# ES_Daisy_Petal_Rev5.net
KiCad netlist of a schematic drawn in EAGLE
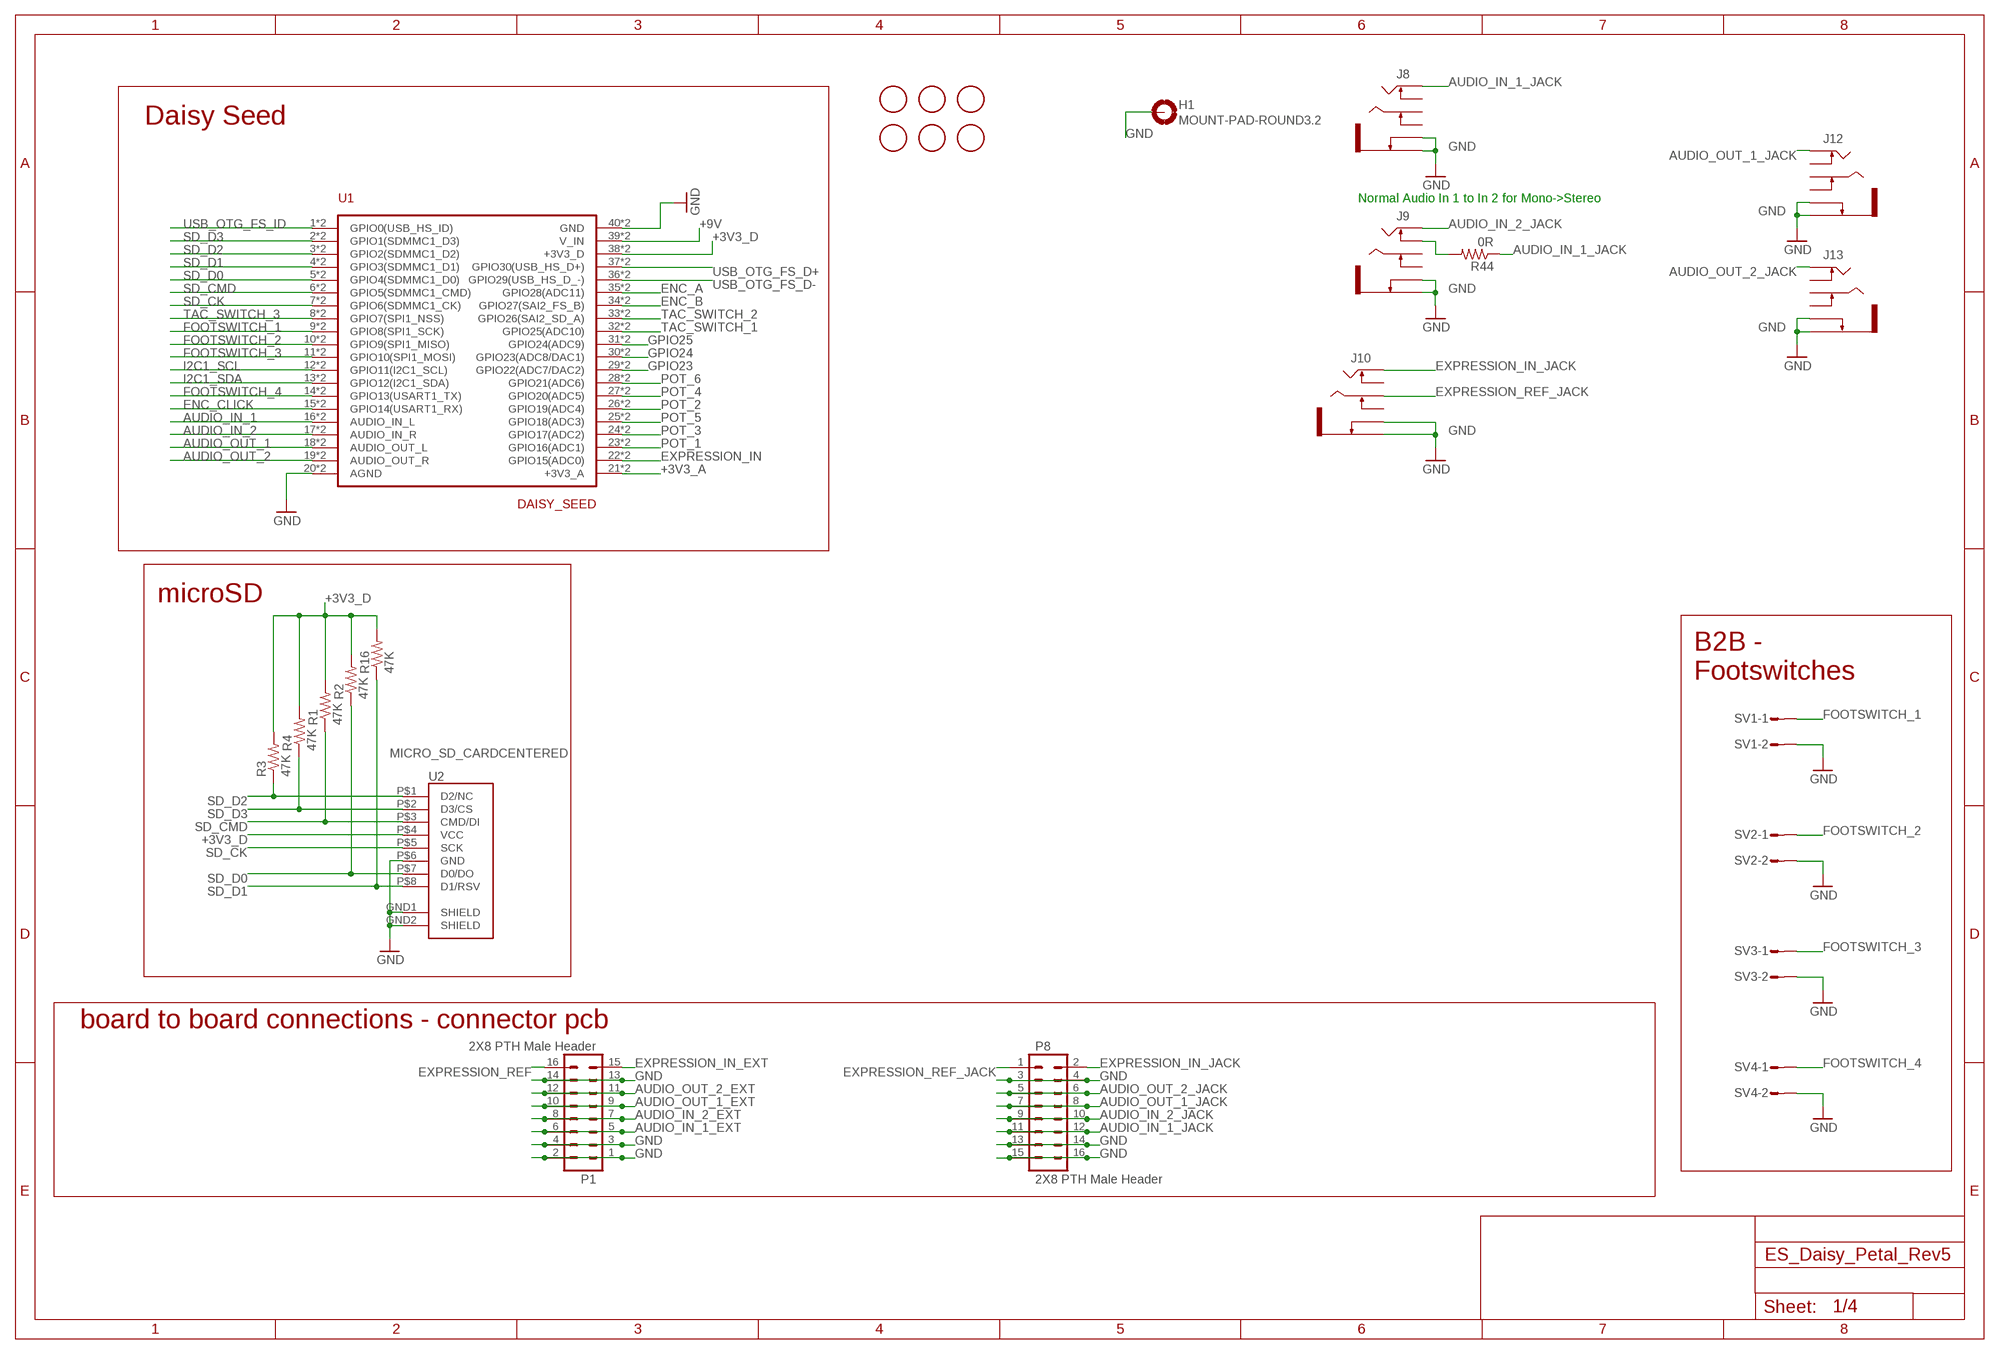
[diagram p0: schematic, sheet 1]
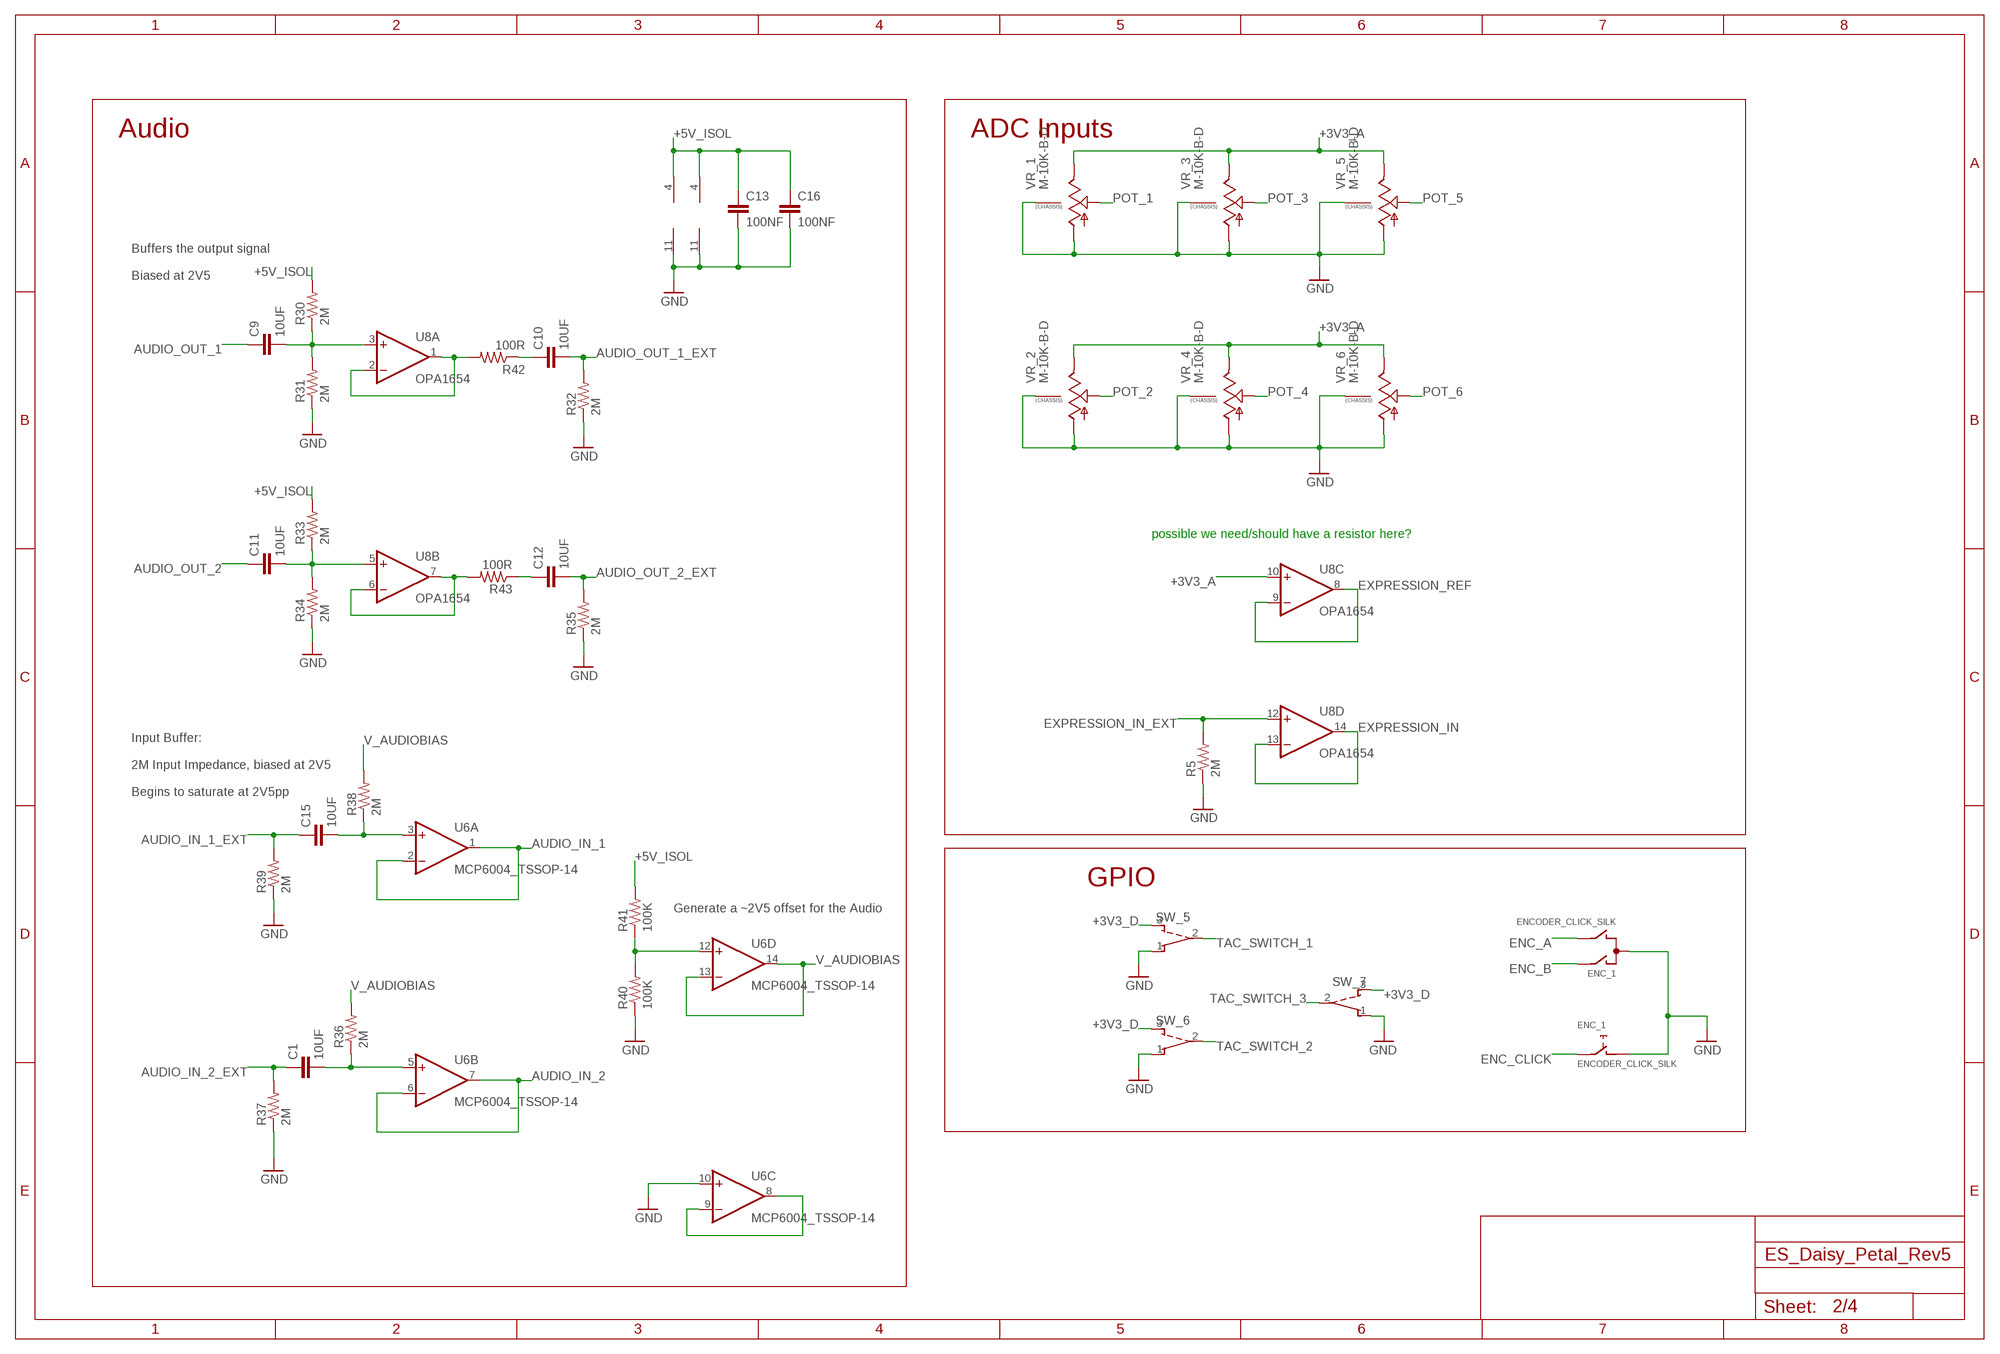
[diagram p1: schematic, sheet 2]
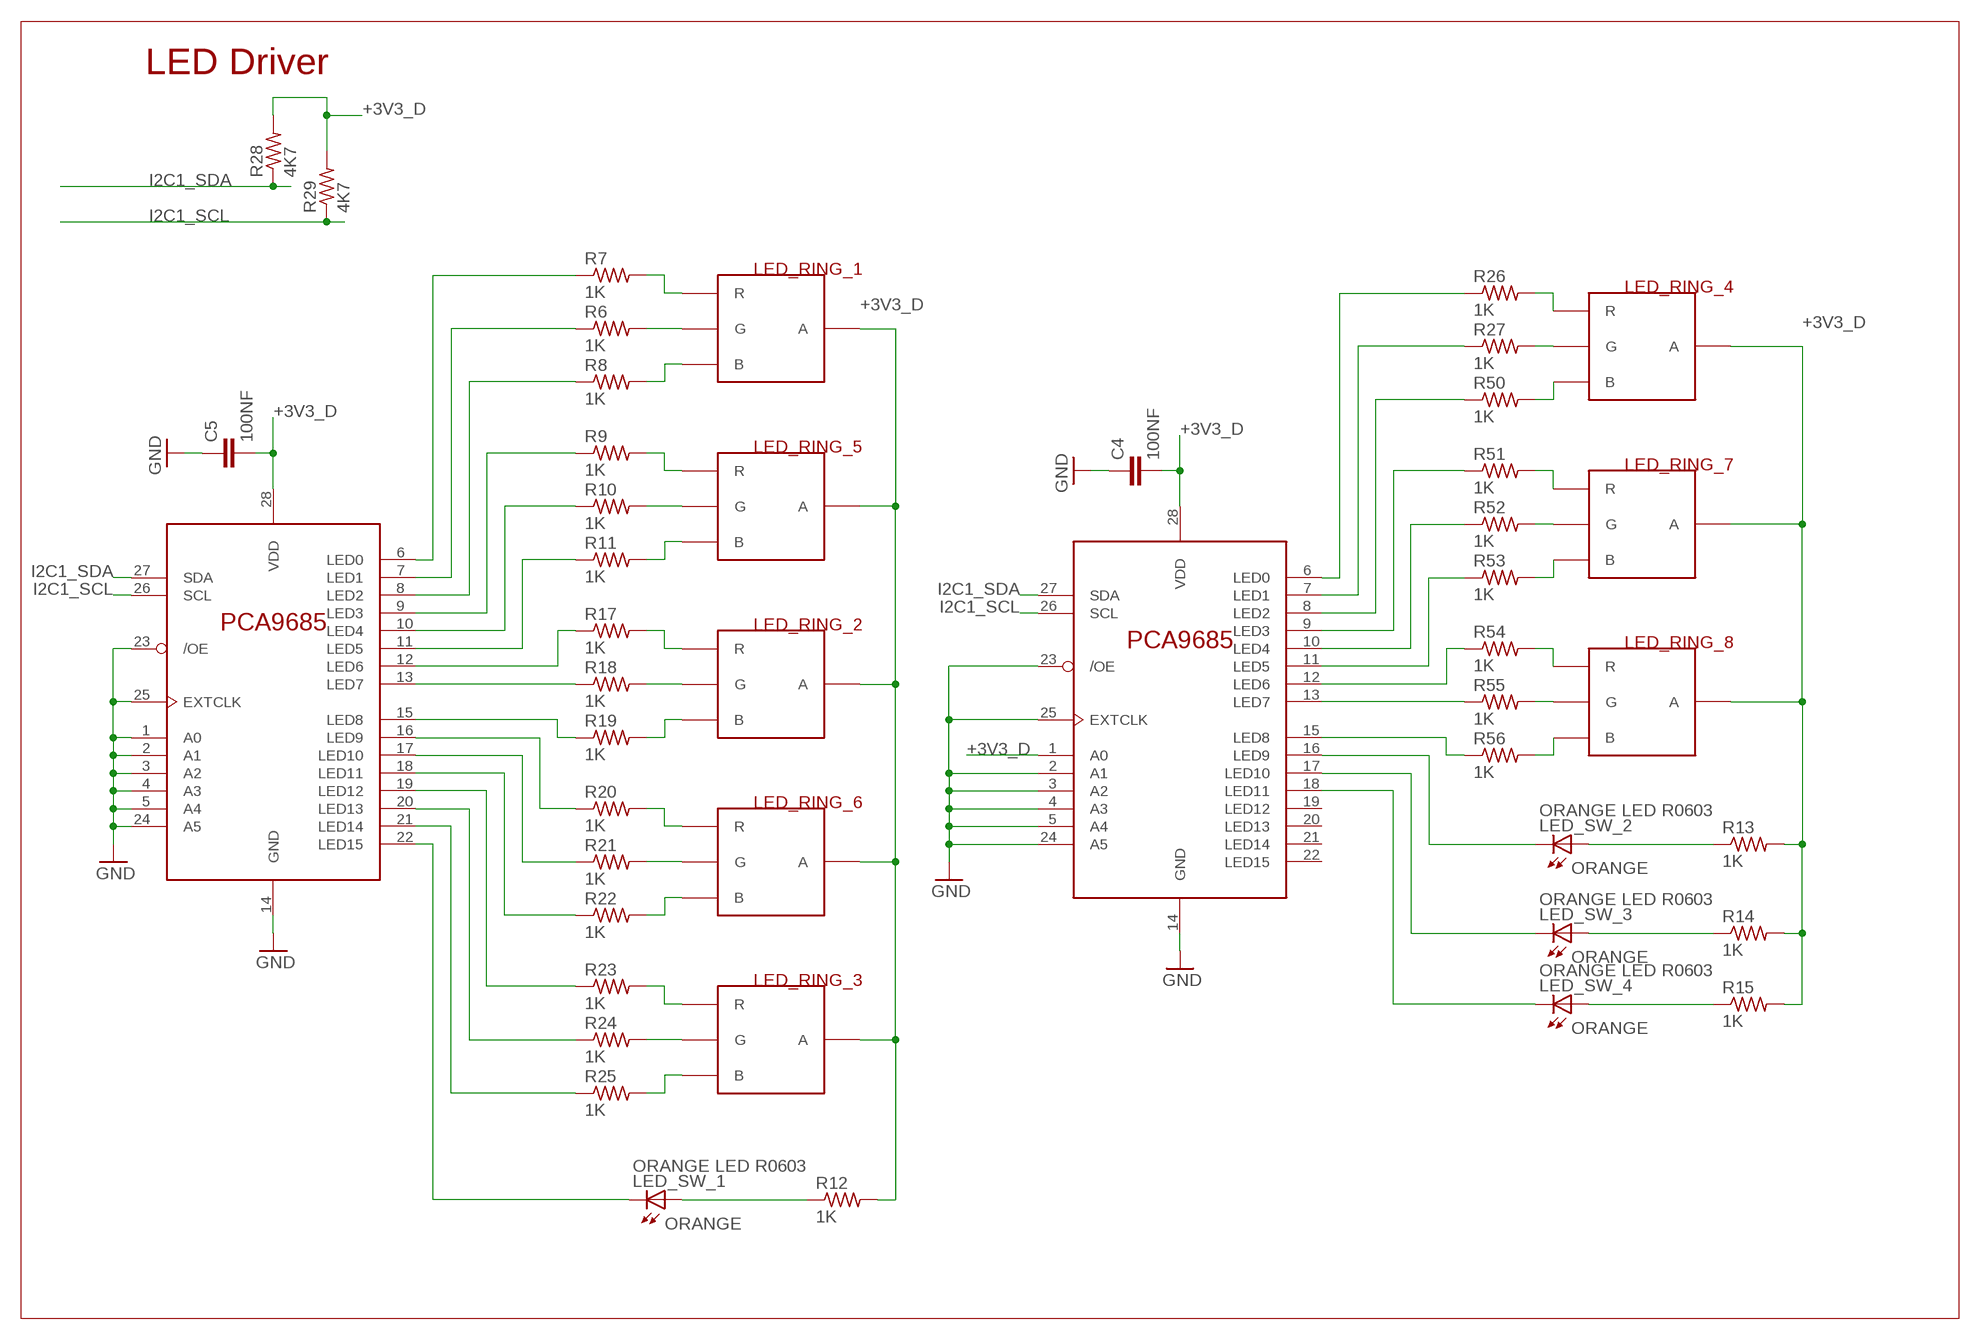
[diagram p2: schematic, sheet 3]
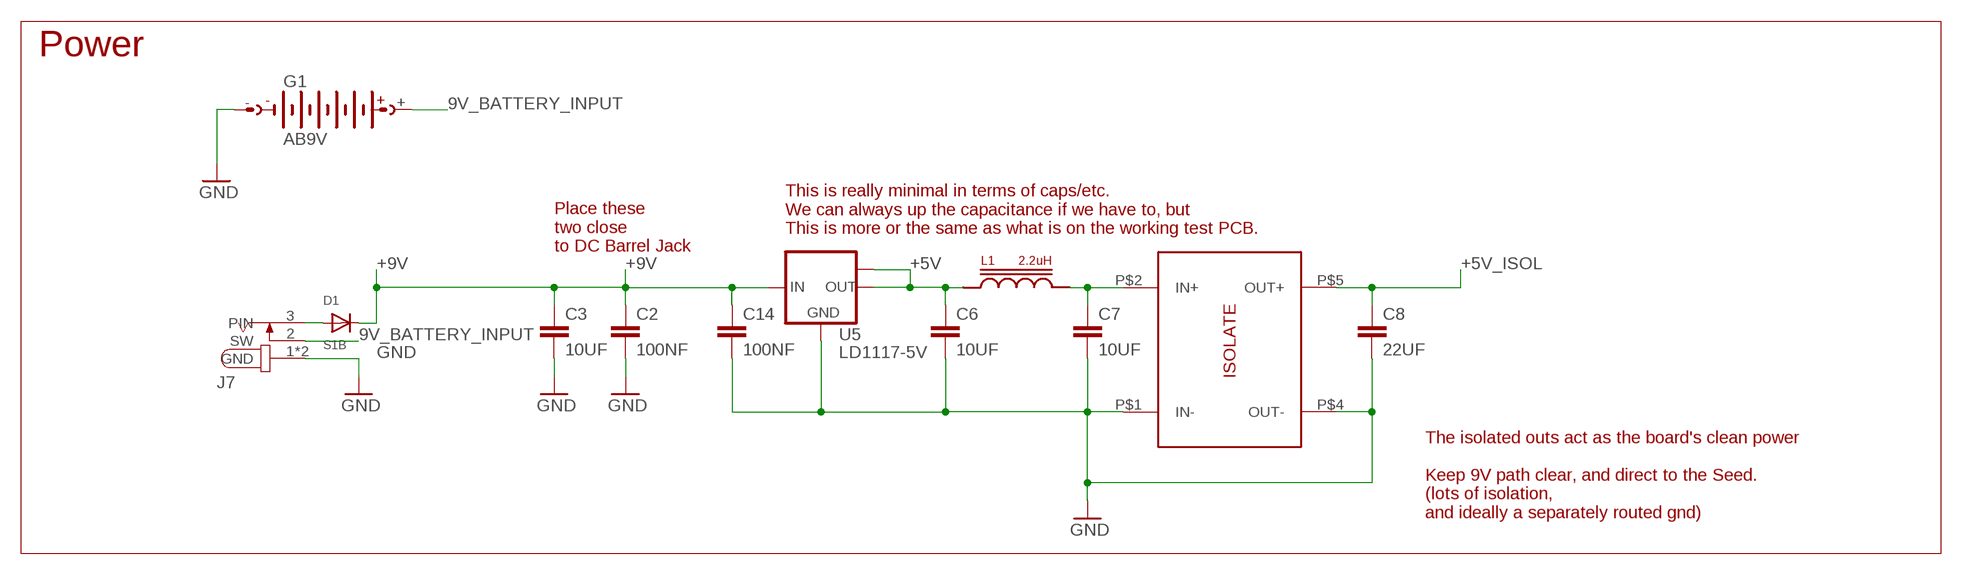
[diagram p3: schematic, sheet 4]

(export (version "E")
  (design (tool "Eeschema 10.0.6"))
  (components
    (comp (ref "FD1")
      (value "FIDUCIAL")
      (footprint "eagle-import:FIDUCIAL_1MM")
      (libsource (lib "eagle-import") (part "FIDUCIAL"))
    )
    (comp (ref "FD2")
      (value "FIDUCIAL")
      (footprint "eagle-import:FIDUCIAL_1MM")
      (libsource (lib "eagle-import") (part "FIDUCIAL"))
    )
    (comp (ref "FD3")
      (value "FIDUCIAL")
      (footprint "eagle-import:FIDUCIAL_1MM")
      (libsource (lib "eagle-import") (part "FIDUCIAL"))
    )
    (comp (ref "FD4")
      (value "FIDUCIAL")
      (footprint "eagle-import:FIDUCIAL_1MM")
      (libsource (lib "eagle-import") (part "FIDUCIAL"))
    )
    (comp (ref "FD5")
      (value "FIDUCIAL")
      (footprint "eagle-import:FIDUCIAL_1MM")
      (libsource (lib "eagle-import") (part "FIDUCIAL"))
    )
    (comp (ref "FD6")
      (value "FIDUCIAL")
      (footprint "eagle-import:FIDUCIAL_1MM")
      (libsource (lib "eagle-import") (part "FIDUCIAL"))
    )
    (comp (ref "H1")
      (value "MOUNT-PAD-ROUND3.2")
      (footprint "eagle-import:3,2-PAD")
      (libsource (lib "eagle-import") (part "MOUNT-PAD-ROUND3.2"))
    )
    (comp (ref "J8")
      (value "JACK_TRS_SWITCHING_WQP-PJ6110")
      (footprint "eagle-import:WQP-PJ6110")
      (libsource (lib "eagle-import") (part "JACK_TRS_SWITCHING_WQP-PJ6110"))
    )
    (comp (ref "J9")
      (value "JACK_TRS_SWITCHING_WQP-PJ6110")
      (footprint "eagle-import:WQP-PJ6110")
      (libsource (lib "eagle-import") (part "JACK_TRS_SWITCHING_WQP-PJ6110"))
    )
    (comp (ref "J10")
      (value "JACK_TRS_SWITCHING_WQP-PJ6110")
      (footprint "eagle-import:WQP-PJ6110")
      (libsource (lib "eagle-import") (part "JACK_TRS_SWITCHING_WQP-PJ6110"))
    )
    (comp (ref "J12")
      (value "JACK_TRS_SWITCHING_WQP-PJ6110")
      (footprint "eagle-import:WQP-PJ6110")
      (libsource (lib "eagle-import") (part "JACK_TRS_SWITCHING_WQP-PJ6110"))
    )
    (comp (ref "J13")
      (value "JACK_TRS_SWITCHING_WQP-PJ6110")
      (footprint "eagle-import:WQP-PJ6110")
      (libsource (lib "eagle-import") (part "JACK_TRS_SWITCHING_WQP-PJ6110"))
    )
    (comp (ref "P1")
      (value "2X8 PTH Male Header")
      (footprint "eagle-import:2X8_SMD")
      (fields (field (name "LABEL") "TO JACK PCB"))
      (libsource (lib "eagle-import") (part "M08X2?"))
    )
    (comp (ref "P8")
      (value "2X8 PTH Male Header")
      (footprint "eagle-import:2X8_LOCK")
      (libsource (lib "eagle-import") (part "M08X2?_LOCK_SILK"))
    )
    (comp (ref "R1")
      (value "47K")
      (footprint "eagle-import:R0603")
      (libsource (lib "eagle-import") (part "R-US_R0603"))
    )
    (comp (ref "R2")
      (value "47K")
      (footprint "eagle-import:R0603")
      (libsource (lib "eagle-import") (part "R-US_R0603"))
    )
    (comp (ref "R3")
      (value "47K")
      (footprint "eagle-import:R0603")
      (libsource (lib "eagle-import") (part "R-US_R0603"))
    )
    (comp (ref "R4")
      (value "47K")
      (footprint "eagle-import:R0603")
      (libsource (lib "eagle-import") (part "R-US_R0603"))
    )
    (comp (ref "R16")
      (value "47K")
      (footprint "eagle-import:R0603")
      (libsource (lib "eagle-import") (part "R-US_R0603"))
    )
    (comp (ref "R44")
      (value "0R")
      (footprint "eagle-import:R0603")
      (libsource (lib "eagle-import") (part "R-US_R0603"))
    )
    (comp (ref "SV1")
      (value "S02P")
      (footprint "eagle-import:S02P")
      (libsource (lib "eagle-import") (part "S02P"))
    )
    (comp (ref "SV2")
      (value "S02P")
      (footprint "eagle-import:S02P")
      (libsource (lib "eagle-import") (part "S02P"))
    )
    (comp (ref "SV3")
      (value "S02P")
      (footprint "eagle-import:S02P")
      (libsource (lib "eagle-import") (part "S02P"))
    )
    (comp (ref "SV4")
      (value "S02P")
      (footprint "eagle-import:S02P")
      (libsource (lib "eagle-import") (part "S02P"))
    )
    (comp (ref "U1")
      (value "DAISY_SEED")
      (footprint "eagle-import:ES_DAISY_SEED_DOUBLE")
      (libsource (lib "eagle-import") (part "ES_DAISY_SEED_REV4_DOUBLE"))
    )
    (comp (ref "U2")
      (value "MICRO_SD_CARDCENTERED")
      (footprint "eagle-import:VERT_MICROSD_CENTERED")
      (libsource (lib "eagle-import") (part "MICRO_SD_CARDCENTERED"))
    )
    (comp (ref "C2")
      (value "100NF")
      (footprint "eagle-import:C0603")
      (libsource (lib "eagle-import") (part "C-EUC0603"))
    )
    (comp (ref "C3")
      (value "10UF")
      (footprint "eagle-import:C0805")
      (libsource (lib "eagle-import") (part "C-EUC0805"))
    )
    (comp (ref "C6")
      (value "10UF")
      (footprint "eagle-import:C0805")
      (libsource (lib "eagle-import") (part "C-EUC0805"))
    )
    (comp (ref "C7")
      (value "10UF")
      (footprint "eagle-import:C0805")
      (libsource (lib "eagle-import") (part "C-EUC0805"))
    )
    (comp (ref "C8")
      (value "22UF")
      (footprint "eagle-import:C1206")
      (libsource (lib "eagle-import") (part "C-EUC1206"))
    )
    (comp (ref "C14")
      (value "100NF")
      (footprint "eagle-import:C0603")
      (libsource (lib "eagle-import") (part "C-EUC0603"))
    )
    (comp (ref "D1")
      (value "S1B")
      (footprint "eagle-import:SMADIODE")
      (libsource (lib "eagle-import") (part "S1B"))
    )
    (comp (ref "G1")
      (value "AB9V")
      (footprint "eagle-import:AB9V")
      (libsource (lib "eagle-import") (part "AB9V"))
    )
    (comp (ref "J7")
      (value "GUITAR_DC_JACK")
      (footprint "eagle-import:WQP-DC0500")
      (libsource (lib "eagle-import") (part "GUITAR_DC_JACK"))
    )
    (comp (ref "L1")
      (value "2.2uH")
      (footprint "eagle-import:BOURNS_SRP2010")
      (libsource (lib "eagle-import") (part "INDUCTORS"))
    )
    (comp (ref "U$3")
      (value "POWER_ISOLATE")
      (footprint "eagle-import:XP_POWER_ISEXXXXA")
      (fields (field (name "MPN") "ISE2405A"))
      (libsource (lib "eagle-import") (part "POWER_ISOLATE"))
    )
    (comp (ref "U5")
      (value "LD1117-5V")
      (footprint "eagle-import:SOT223")
      (fields (field (name "MPN") "LD1117S50CTR"))
      (libsource (lib "eagle-import") (part "LD1117-5V"))
    )
    (comp (ref "C4")
      (value "100NF")
      (footprint "eagle-import:C0603")
      (libsource (lib "eagle-import") (part "C-EUC0603"))
    )
    (comp (ref "C5")
      (value "100NF")
      (footprint "eagle-import:C0603")
      (libsource (lib "eagle-import") (part "C-EUC0603"))
    )
    (comp (ref "LED_RING_1")
      (value "RGB LED SMT PLCC4")
      (footprint "eagle-import:P-LCC-4-3")
      (fields (field (name "MPN") "CLVBA-FKA-CC1F1L1BB7R3R3"))
      (libsource (lib "eagle-import") (part "LED_RGB_SMT"))
    )
    (comp (ref "LED_RING_2")
      (value "RGB LED SMT PLCC4")
      (footprint "eagle-import:P-LCC-4-3")
      (fields (field (name "MPN") "CLVBA-FKA-CC1F1L1BB7R3R3"))
      (libsource (lib "eagle-import") (part "LED_RGB_SMT"))
    )
    (comp (ref "LED_RING_3")
      (value "RGB LED SMT PLCC4")
      (footprint "eagle-import:P-LCC-4-3")
      (fields (field (name "MPN") "CLVBA-FKA-CC1F1L1BB7R3R3"))
      (libsource (lib "eagle-import") (part "LED_RGB_SMT"))
    )
    (comp (ref "LED_RING_4")
      (value "RGB LED SMT PLCC4")
      (footprint "eagle-import:P-LCC-4-3")
      (fields (field (name "MPN") "CLVBA-FKA-CC1F1L1BB7R3R3"))
      (libsource (lib "eagle-import") (part "LED_RGB_SMT"))
    )
    (comp (ref "LED_RING_5")
      (value "RGB LED SMT PLCC4")
      (footprint "eagle-import:P-LCC-4-3")
      (fields (field (name "MPN") "CLVBA-FKA-CC1F1L1BB7R3R3"))
      (libsource (lib "eagle-import") (part "LED_RGB_SMT"))
    )
    (comp (ref "LED_RING_6")
      (value "RGB LED SMT PLCC4")
      (footprint "eagle-import:P-LCC-4-3")
      (fields (field (name "MPN") "CLVBA-FKA-CC1F1L1BB7R3R3"))
      (libsource (lib "eagle-import") (part "LED_RGB_SMT"))
    )
    (comp (ref "LED_RING_7")
      (value "RGB LED SMT PLCC4")
      (footprint "eagle-import:P-LCC-4-3")
      (fields (field (name "MPN") "CLVBA-FKA-CC1F1L1BB7R3R3"))
      (libsource (lib "eagle-import") (part "LED_RGB_SMT"))
    )
    (comp (ref "LED_RING_8")
      (value "RGB LED SMT PLCC4")
      (footprint "eagle-import:P-LCC-4-3")
      (fields (field (name "MPN") "CLVBA-FKA-CC1F1L1BB7R3R3"))
      (libsource (lib "eagle-import") (part "LED_RGB_SMT"))
    )
    (comp (ref "LED_SW_1")
      (value "ORANGE LED R0603")
      (footprint "eagle-import:DIODE_0603")
      (fields (field (name "COLOR") "ORANGE") (field (name "MPN") "APT1608LSECK/J4-PRV"))
      (libsource (lib "eagle-import") (part "LED_0603_ORANGE"))
    )
    (comp (ref "LED_SW_2")
      (value "ORANGE LED R0603")
      (footprint "eagle-import:DIODE_0603")
      (fields (field (name "COLOR") "ORANGE") (field (name "MPN") "APT1608LSECK/J4-PRV"))
      (libsource (lib "eagle-import") (part "LED_0603_ORANGE"))
    )
    (comp (ref "LED_SW_3")
      (value "ORANGE LED R0603")
      (footprint "eagle-import:DIODE_0603")
      (fields (field (name "COLOR") "ORANGE") (field (name "MPN") "APT1608LSECK/J4-PRV"))
      (libsource (lib "eagle-import") (part "LED_0603_ORANGE"))
    )
    (comp (ref "LED_SW_4")
      (value "ORANGE LED R0603")
      (footprint "eagle-import:DIODE_0603")
      (fields (field (name "COLOR") "ORANGE") (field (name "MPN") "APT1608LSECK/J4-PRV"))
      (libsource (lib "eagle-import") (part "LED_0603_ORANGE"))
    )
    (comp (ref "R6")
      (value "1K")
      (footprint "eagle-import:R0603")
      (libsource (lib "eagle-import") (part "R-US_R0603"))
    )
    (comp (ref "R7")
      (value "1K")
      (footprint "eagle-import:R0603")
      (libsource (lib "eagle-import") (part "R-US_R0603"))
    )
    (comp (ref "R8")
      (value "1K")
      (footprint "eagle-import:R0603")
      (libsource (lib "eagle-import") (part "R-US_R0603"))
    )
    (comp (ref "R9")
      (value "1K")
      (footprint "eagle-import:R0603")
      (libsource (lib "eagle-import") (part "R-US_R0603"))
    )
    (comp (ref "R10")
      (value "1K")
      (footprint "eagle-import:R0603")
      (libsource (lib "eagle-import") (part "R-US_R0603"))
    )
    (comp (ref "R11")
      (value "1K")
      (footprint "eagle-import:R0603")
      (libsource (lib "eagle-import") (part "R-US_R0603"))
    )
    (comp (ref "R12")
      (value "1K")
      (footprint "eagle-import:R0603")
      (libsource (lib "eagle-import") (part "R-US_R0603"))
    )
    (comp (ref "R13")
      (value "1K")
      (footprint "eagle-import:R0603")
      (libsource (lib "eagle-import") (part "R-US_R0603"))
    )
    (comp (ref "R14")
      (value "1K")
      (footprint "eagle-import:R0603")
      (libsource (lib "eagle-import") (part "R-US_R0603"))
    )
    (comp (ref "R15")
      (value "1K")
      (footprint "eagle-import:R0603")
      (libsource (lib "eagle-import") (part "R-US_R0603"))
    )
    (comp (ref "R17")
      (value "1K")
      (footprint "eagle-import:R0603")
      (libsource (lib "eagle-import") (part "R-US_R0603"))
    )
    (comp (ref "R18")
      (value "1K")
      (footprint "eagle-import:R0603")
      (libsource (lib "eagle-import") (part "R-US_R0603"))
    )
    (comp (ref "R19")
      (value "1K")
      (footprint "eagle-import:R0603")
      (libsource (lib "eagle-import") (part "R-US_R0603"))
    )
    (comp (ref "R20")
      (value "1K")
      (footprint "eagle-import:R0603")
      (libsource (lib "eagle-import") (part "R-US_R0603"))
    )
    (comp (ref "R21")
      (value "1K")
      (footprint "eagle-import:R0603")
      (libsource (lib "eagle-import") (part "R-US_R0603"))
    )
    (comp (ref "R22")
      (value "1K")
      (footprint "eagle-import:R0603")
      (libsource (lib "eagle-import") (part "R-US_R0603"))
    )
    (comp (ref "R23")
      (value "1K")
      (footprint "eagle-import:R0603")
      (libsource (lib "eagle-import") (part "R-US_R0603"))
    )
    (comp (ref "R24")
      (value "1K")
      (footprint "eagle-import:R0603")
      (libsource (lib "eagle-import") (part "R-US_R0603"))
    )
    (comp (ref "R25")
      (value "1K")
      (footprint "eagle-import:R0603")
      (libsource (lib "eagle-import") (part "R-US_R0603"))
    )
    (comp (ref "R26")
      (value "1K")
      (footprint "eagle-import:R0603")
      (libsource (lib "eagle-import") (part "R-US_R0603"))
    )
    (comp (ref "R27")
      (value "1K")
      (footprint "eagle-import:R0603")
      (libsource (lib "eagle-import") (part "R-US_R0603"))
    )
    (comp (ref "R28")
      (value "4K7")
      (footprint "eagle-import:R0603")
      (libsource (lib "eagle-import") (part "R-US_R0603"))
    )
    (comp (ref "R29")
      (value "4K7")
      (footprint "eagle-import:R0603")
      (libsource (lib "eagle-import") (part "R-US_R0603"))
    )
    (comp (ref "R50")
      (value "1K")
      (footprint "eagle-import:R0603")
      (libsource (lib "eagle-import") (part "R-US_R0603"))
    )
    (comp (ref "R51")
      (value "1K")
      (footprint "eagle-import:R0603")
      (libsource (lib "eagle-import") (part "R-US_R0603"))
    )
    (comp (ref "R52")
      (value "1K")
      (footprint "eagle-import:R0603")
      (libsource (lib "eagle-import") (part "R-US_R0603"))
    )
    (comp (ref "R53")
      (value "1K")
      (footprint "eagle-import:R0603")
      (libsource (lib "eagle-import") (part "R-US_R0603"))
    )
    (comp (ref "R54")
      (value "1K")
      (footprint "eagle-import:R0603")
      (libsource (lib "eagle-import") (part "R-US_R0603"))
    )
    (comp (ref "R55")
      (value "1K")
      (footprint "eagle-import:R0603")
      (libsource (lib "eagle-import") (part "R-US_R0603"))
    )
    (comp (ref "R56")
      (value "1K")
      (footprint "eagle-import:R0603")
      (libsource (lib "eagle-import") (part "R-US_R0603"))
    )
    (comp (ref "U3")
      (value "PCA9685PW")
      (footprint "eagle-import:TSSOP-28")
      (fields (field (name "MPN") "PCA9685PW,118"))
      (libsource (lib "eagle-import") (part "PCA9685PW"))
    )
    (comp (ref "U4")
      (value "PCA9685PW")
      (footprint "eagle-import:TSSOP-28")
      (fields (field (name "MPN") "PCA9685PW,118"))
      (libsource (lib "eagle-import") (part "PCA9685PW"))
    )
    (comp (ref "C1")
      (value "10UF")
      (footprint "eagle-import:C0805")
      (libsource (lib "eagle-import") (part "C-EUC0805"))
    )
    (comp (ref "C9")
      (value "10UF")
      (footprint "eagle-import:C0805")
      (libsource (lib "eagle-import") (part "C-EUC0805"))
    )
    (comp (ref "C10")
      (value "10UF")
      (footprint "eagle-import:C0805")
      (libsource (lib "eagle-import") (part "C-EUC0805"))
    )
    (comp (ref "C11")
      (value "10UF")
      (footprint "eagle-import:C0805")
      (libsource (lib "eagle-import") (part "C-EUC0805"))
    )
    (comp (ref "C12")
      (value "10UF")
      (footprint "eagle-import:C0805")
      (libsource (lib "eagle-import") (part "C-EUC0805"))
    )
    (comp (ref "C13")
      (value "100NF")
      (footprint "eagle-import:C0603")
      (libsource (lib "eagle-import") (part "C-EUC0603"))
    )
    (comp (ref "C15")
      (value "10UF")
      (footprint "eagle-import:C0805")
      (libsource (lib "eagle-import") (part "C-EUC0805"))
    )
    (comp (ref "C16")
      (value "100NF")
      (footprint "eagle-import:C0603")
      (libsource (lib "eagle-import") (part "C-EUC0603"))
    )
    (comp (ref "ENC_1")
      (value "ENCODER_CLICK_SILK")
      (footprint "eagle-import:PEC11_SILK")
      (libsource (lib "eagle-import") (part "ENCODERSILK_CLICK_"))
    )
    (comp (ref "R5")
      (value "2M")
      (footprint "eagle-import:R0603")
      (libsource (lib "eagle-import") (part "R-US_R0603"))
    )
    (comp (ref "R30")
      (value "2M")
      (footprint "eagle-import:R0603")
      (libsource (lib "eagle-import") (part "R-US_R0603"))
    )
    (comp (ref "R31")
      (value "2M")
      (footprint "eagle-import:R0603")
      (libsource (lib "eagle-import") (part "R-US_R0603"))
    )
    (comp (ref "R32")
      (value "2M")
      (footprint "eagle-import:R0603")
      (libsource (lib "eagle-import") (part "R-US_R0603"))
    )
    (comp (ref "R33")
      (value "2M")
      (footprint "eagle-import:R0603")
      (libsource (lib "eagle-import") (part "R-US_R0603"))
    )
    (comp (ref "R34")
      (value "2M")
      (footprint "eagle-import:R0603")
      (libsource (lib "eagle-import") (part "R-US_R0603"))
    )
    (comp (ref "R35")
      (value "2M")
      (footprint "eagle-import:R0603")
      (libsource (lib "eagle-import") (part "R-US_R0603"))
    )
    (comp (ref "R36")
      (value "2M")
      (footprint "eagle-import:R0603")
      (libsource (lib "eagle-import") (part "R-US_R0603"))
    )
    (comp (ref "R37")
      (value "2M")
      (footprint "eagle-import:R0603")
      (libsource (lib "eagle-import") (part "R-US_R0603"))
    )
    (comp (ref "R38")
      (value "2M")
      (footprint "eagle-import:R0603")
      (libsource (lib "eagle-import") (part "R-US_R0603"))
    )
    (comp (ref "R39")
      (value "2M")
      (footprint "eagle-import:R0603")
      (libsource (lib "eagle-import") (part "R-US_R0603"))
    )
    (comp (ref "R40")
      (value "100K")
      (footprint "eagle-import:R0603")
      (libsource (lib "eagle-import") (part "R-US_R0603"))
    )
    (comp (ref "R41")
      (value "100K")
      (footprint "eagle-import:R0603")
      (libsource (lib "eagle-import") (part "R-US_R0603"))
    )
    (comp (ref "R42")
      (value "100R")
      (footprint "eagle-import:R0603")
      (libsource (lib "eagle-import") (part "R-US_R0603"))
    )
    (comp (ref "R43")
      (value "100R")
      (footprint "eagle-import:R0603")
      (libsource (lib "eagle-import") (part "R-US_R0603"))
    )
    (comp (ref "SW_5")
      (value "TOGGLE_ON-ON_PIN_IN_PASTE")
      (footprint "eagle-import:TOGGLE_SILK_PIP")
      (libsource (lib "eagle-import") (part "TOGGLE_ON-ON_PIN_IN_PASTE"))
    )
    (comp (ref "SW_6")
      (value "TOGGLE_ON-ON_PIN_IN_PASTE")
      (footprint "eagle-import:TOGGLE_SILK_PIP")
      (libsource (lib "eagle-import") (part "TOGGLE_ON-ON_PIN_IN_PASTE"))
    )
    (comp (ref "SW_7")
      (value "TOGGLE_ON-ON_PIN_IN_PASTE")
      (footprint "eagle-import:TOGGLE_SILK_PIP")
      (libsource (lib "eagle-import") (part "TOGGLE_ON-ON_PIN_IN_PASTE"))
    )
    (comp (ref "U6")
      (value "MCP6004_TSSOP-14")
      (footprint "eagle-import:TSSOP-14")
      (fields (field (name "MPN") "MCP6004T-E/ST"))
      (libsource (lib "eagle-import") (part "MCP6004_TSSOP-14"))
    )
    (comp (ref "U8")
      (value "OPA1654")
      (footprint "eagle-import:TSSOP-14")
      (libsource (lib "eagle-import") (part "OPA1654_TSSOP-14"))
    )
    (comp (ref "VR_1")
      (value "M-10K-B-D")
      (footprint "eagle-import:9MM_SNAP-IN_POT_SILK")
      (libsource (lib "eagle-import") (part "POT_9MM_CHASSIS_"))
    )
    (comp (ref "VR_2")
      (value "M-10K-B-D")
      (footprint "eagle-import:9MM_SNAP-IN_POT_SILK")
      (libsource (lib "eagle-import") (part "POT_9MM_CHASSIS_"))
    )
    (comp (ref "VR_3")
      (value "M-10K-B-D")
      (footprint "eagle-import:9MM_SNAP-IN_POT_SILK")
      (libsource (lib "eagle-import") (part "POT_9MM_CHASSIS_"))
    )
    (comp (ref "VR_4")
      (value "M-10K-B-D")
      (footprint "eagle-import:9MM_SNAP-IN_POT_SILK")
      (libsource (lib "eagle-import") (part "POT_9MM_CHASSIS_"))
    )
    (comp (ref "VR_5")
      (value "M-10K-B-D")
      (footprint "eagle-import:9MM_SNAP-IN_POT_SILK")
      (libsource (lib "eagle-import") (part "POT_9MM_CHASSIS_"))
    )
    (comp (ref "VR_6")
      (value "M-10K-B-D")
      (footprint "eagle-import:9MM_SNAP-IN_POT_SILK")
      (libsource (lib "eagle-import") (part "POT_9MM_CHASSIS_"))
    )
  )
  (nets
    (net (code "1") (name "+3V3_A") (class "Default")
      (node (ref "U1") (pin "21") (pinfunction "+3V3_A_21") (pintype "bidirectional"))
      (node (ref "U1") (pin "B21") (pinfunction "+3V3_A_B21") (pintype "bidirectional"))
      (node (ref "U8") (pin "10") (pinfunction "+IN_10") (pintype "input"))
      (node (ref "VR_1") (pin "3") (pinfunction "E_3") (pintype "passive"))
      (node (ref "VR_2") (pin "3") (pinfunction "E_3") (pintype "passive"))
      (node (ref "VR_3") (pin "3") (pinfunction "E_3") (pintype "passive"))
      (node (ref "VR_4") (pin "3") (pinfunction "E_3") (pintype "passive"))
      (node (ref "VR_5") (pin "3") (pinfunction "E_3") (pintype "passive"))
      (node (ref "VR_6") (pin "3") (pinfunction "E_3") (pintype "passive"))
    )
    (net (code "2") (name "+3V3_D") (class "Default")
      (node (ref "C4") (pin "2") (pinfunction "2_2") (pintype "passive"))
      (node (ref "C5") (pin "2") (pinfunction "2_2") (pintype "passive"))
      (node (ref "LED_RING_1") (pin "2") (pinfunction "A_2") (pintype "bidirectional"))
      (node (ref "LED_RING_2") (pin "2") (pinfunction "A_2") (pintype "bidirectional"))
      (node (ref "LED_RING_3") (pin "2") (pinfunction "A_2") (pintype "bidirectional"))
      (node (ref "LED_RING_4") (pin "2") (pinfunction "A_2") (pintype "bidirectional"))
      (node (ref "LED_RING_5") (pin "2") (pinfunction "A_2") (pintype "bidirectional"))
      (node (ref "LED_RING_6") (pin "2") (pinfunction "A_2") (pintype "bidirectional"))
      (node (ref "LED_RING_7") (pin "2") (pinfunction "A_2") (pintype "bidirectional"))
      (node (ref "LED_RING_8") (pin "2") (pinfunction "A_2") (pintype "bidirectional"))
      (node (ref "R1") (pin "2") (pinfunction "2_2") (pintype "passive"))
      (node (ref "R12") (pin "2") (pinfunction "2_2") (pintype "passive"))
      (node (ref "R13") (pin "2") (pinfunction "2_2") (pintype "passive"))
      (node (ref "R14") (pin "2") (pinfunction "2_2") (pintype "passive"))
      (node (ref "R15") (pin "2") (pinfunction "2_2") (pintype "passive"))
      (node (ref "R16") (pin "2") (pinfunction "2_2") (pintype "passive"))
      (node (ref "R2") (pin "2") (pinfunction "2_2") (pintype "passive"))
      (node (ref "R28") (pin "2") (pinfunction "2_2") (pintype "passive"))
      (node (ref "R29") (pin "2") (pinfunction "2_2") (pintype "passive"))
      (node (ref "R3") (pin "2") (pinfunction "2_2") (pintype "passive"))
      (node (ref "R4") (pin "2") (pinfunction "2_2") (pintype "passive"))
      (node (ref "SW_5") (pin "3") (pinfunction "S_3") (pintype "passive"))
      (node (ref "SW_6") (pin "3") (pinfunction "S_3") (pintype "passive"))
      (node (ref "SW_7") (pin "3") (pinfunction "S_3") (pintype "passive"))
      (node (ref "U1") (pin "38") (pinfunction "+3V3_D_38") (pintype "bidirectional"))
      (node (ref "U1") (pin "B38") (pinfunction "+3V3_D_B38") (pintype "bidirectional"))
      (node (ref "U2") (pin "P$4") (pinfunction "VCC_P$4") (pintype "bidirectional"))
      (node (ref "U3") (pin "1") (pinfunction "A0_1") (pintype "bidirectional"))
      (node (ref "U3") (pin "28") (pinfunction "VDD_28") (pintype "power_in"))
      (node (ref "U4") (pin "28") (pinfunction "VDD_28") (pintype "power_in"))
    )
    (net (code "3") (name "+5V") (class "Default")
      (node (ref "C6") (pin "1") (pinfunction "1_1") (pintype "passive"))
      (node (ref "L1") (pin "P$1") (pinfunction "P$1_P$1") (pintype "bidirectional"))
      (node (ref "U5") (pin "2") (pinfunction "OUT_2") (pintype "passive"))
      (node (ref "U5") (pin "TAB") (pinfunction "OUT1_TAB") (pintype "passive"))
    )
    (net (code "4") (name "+5V_ISOL") (class "Default")
      (node (ref "C13") (pin "1") (pinfunction "1_1") (pintype "passive"))
      (node (ref "C16") (pin "1") (pinfunction "1_1") (pintype "passive"))
      (node (ref "C8") (pin "1") (pinfunction "1_1") (pintype "passive"))
      (node (ref "R30") (pin "2") (pinfunction "2_2") (pintype "passive"))
      (node (ref "R33") (pin "2") (pinfunction "2_2") (pintype "passive"))
      (node (ref "R41") (pin "2") (pinfunction "2_2") (pintype "passive"))
      (node (ref "U$3") (pin "P$5") (pinfunction "OUT+_P$5") (pintype "bidirectional"))
      (node (ref "U6") (pin "4") (pinfunction "V+_4") (pintype "power_in"))
      (node (ref "U8") (pin "4") (pinfunction "V+_4") (pintype "power_in"))
    )
    (net (code "5") (name "+9V") (class "Default")
      (node (ref "C14") (pin "1") (pinfunction "1_1") (pintype "passive"))
      (node (ref "C2") (pin "1") (pinfunction "1_1") (pintype "passive"))
      (node (ref "C3") (pin "1") (pinfunction "1_1") (pintype "passive"))
      (node (ref "D1") (pin "C") (pinfunction "C_C") (pintype "passive"))
      (node (ref "U1") (pin "39") (pinfunction "V_IN_39") (pintype "bidirectional"))
      (node (ref "U1") (pin "B39") (pinfunction "V_IN_B39") (pintype "bidirectional"))
      (node (ref "U5") (pin "3") (pinfunction "IN_3") (pintype "input"))
    )
    (net (code "6") (name "9V_BATTERY_INPUT") (class "Default")
      (node (ref "G1") (pin "+") (pinfunction "+_+") (pintype "passive"))
      (node (ref "J7") (pin "2") (pinfunction "SW_2") (pintype "passive"))
    )
    (net (code "7") (name "AUDIO_IN_1") (class "Default")
      (node (ref "U1") (pin "16") (pinfunction "AUDIO_IN_L_16") (pintype "bidirectional"))
      (node (ref "U1") (pin "B16") (pinfunction "AUDIO_IN_L_B16") (pintype "bidirectional"))
      (node (ref "U6") (pin "1") (pinfunction "OUT_1") (pintype "output"))
      (node (ref "U6") (pin "2") (pinfunction "-IN_2") (pintype "input"))
    )
    (net (code "8") (name "AUDIO_IN_1_EXT") (class "Default")
      (node (ref "C15") (pin "1") (pinfunction "1_1") (pintype "passive"))
      (node (ref "P1") (pin "5") (pinfunction "5_5") (pintype "passive"))
      (node (ref "P1") (pin "6") (pinfunction "6_6") (pintype "passive"))
      (node (ref "R39") (pin "2") (pinfunction "2_2") (pintype "passive"))
    )
    (net (code "9") (name "AUDIO_IN_1_JACK") (class "Default")
      (node (ref "J8") (pin "2") (pinfunction "TIP_2") (pintype "passive"))
      (node (ref "P8") (pin "11") (pinfunction "11_11") (pintype "passive"))
      (node (ref "P8") (pin "12") (pinfunction "12_12") (pintype "passive"))
      (node (ref "R44") (pin "1") (pinfunction "1_1") (pintype "passive"))
    )
    (net (code "10") (name "AUDIO_IN_2") (class "Default")
      (node (ref "U1") (pin "17") (pinfunction "AUDIO_IN_R_17") (pintype "bidirectional"))
      (node (ref "U1") (pin "B17") (pinfunction "AUDIO_IN_R_B17") (pintype "bidirectional"))
      (node (ref "U6") (pin "6") (pinfunction "-IN_6") (pintype "input"))
      (node (ref "U6") (pin "7") (pinfunction "OUT_7") (pintype "output"))
    )
    (net (code "11") (name "AUDIO_IN_2_EXT") (class "Default")
      (node (ref "C1") (pin "1") (pinfunction "1_1") (pintype "passive"))
      (node (ref "P1") (pin "7") (pinfunction "7_7") (pintype "passive"))
      (node (ref "P1") (pin "8") (pinfunction "8_8") (pintype "passive"))
      (node (ref "R37") (pin "2") (pinfunction "2_2") (pintype "passive"))
    )
    (net (code "12") (name "AUDIO_IN_2_JACK") (class "Default")
      (node (ref "J9") (pin "2") (pinfunction "TIP_2") (pintype "passive"))
      (node (ref "P8") (pin "10") (pinfunction "10_10") (pintype "passive"))
      (node (ref "P8") (pin "9") (pinfunction "9_9") (pintype "passive"))
    )
    (net (code "13") (name "AUDIO_OUT_1") (class "Default")
      (node (ref "C9") (pin "1") (pinfunction "1_1") (pintype "passive"))
      (node (ref "U1") (pin "18") (pinfunction "AUDIO_OUT_L_18") (pintype "bidirectional"))
      (node (ref "U1") (pin "B18") (pinfunction "AUDIO_OUT_L_B18") (pintype "bidirectional"))
    )
    (net (code "14") (name "AUDIO_OUT_1_EXT") (class "Default")
      (node (ref "C10") (pin "2") (pinfunction "2_2") (pintype "passive"))
      (node (ref "P1") (pin "10") (pinfunction "10_10") (pintype "passive"))
      (node (ref "P1") (pin "9") (pinfunction "9_9") (pintype "passive"))
      (node (ref "R32") (pin "2") (pinfunction "2_2") (pintype "passive"))
    )
    (net (code "15") (name "AUDIO_OUT_1_JACK") (class "Default")
      (node (ref "J12") (pin "2") (pinfunction "TIP_2") (pintype "passive"))
      (node (ref "P8") (pin "7") (pinfunction "7_7") (pintype "passive"))
      (node (ref "P8") (pin "8") (pinfunction "8_8") (pintype "passive"))
    )
    (net (code "16") (name "AUDIO_OUT_2") (class "Default")
      (node (ref "C11") (pin "1") (pinfunction "1_1") (pintype "passive"))
      (node (ref "U1") (pin "19") (pinfunction "AUDIO_OUT_R_19") (pintype "bidirectional"))
      (node (ref "U1") (pin "B19") (pinfunction "AUDIO_OUT_R_B19") (pintype "bidirectional"))
    )
    (net (code "17") (name "AUDIO_OUT_2_EXT") (class "Default")
      (node (ref "C12") (pin "2") (pinfunction "2_2") (pintype "passive"))
      (node (ref "P1") (pin "11") (pinfunction "11_11") (pintype "passive"))
      (node (ref "P1") (pin "12") (pinfunction "12_12") (pintype "passive"))
      (node (ref "R35") (pin "2") (pinfunction "2_2") (pintype "passive"))
    )
    (net (code "18") (name "AUDIO_OUT_2_JACK") (class "Default")
      (node (ref "J13") (pin "2") (pinfunction "TIP_2") (pintype "passive"))
      (node (ref "P8") (pin "5") (pinfunction "5_5") (pintype "passive"))
      (node (ref "P8") (pin "6") (pinfunction "6_6") (pintype "passive"))
    )
    (net (code "19") (name "ENC_A") (class "Default")
      (node (ref "ENC_1") (pin "B") (pinfunction "B_B") (pintype "passive"))
      (node (ref "U1") (pin "35") (pinfunction "GPIO28(ADC11)_35") (pintype "bidirectional"))
      (node (ref "U1") (pin "B35") (pinfunction "GPIO28(ADC11)_B35") (pintype "bidirectional"))
    )
    (net (code "20") (name "ENC_B") (class "Default")
      (node (ref "ENC_1") (pin "A") (pinfunction "A_A") (pintype "passive"))
      (node (ref "U1") (pin "34") (pinfunction "GPIO27(SAI2_FS_B)_34") (pintype "bidirectional"))
      (node (ref "U1") (pin "B34") (pinfunction "GPIO27(SAI2_FS_B)_B34") (pintype "bidirectional"))
    )
    (net (code "21") (name "ENC_CLICK") (class "Default")
      (node (ref "ENC_1") (pin "E") (pinfunction "2_E") (pintype "passive"))
      (node (ref "U1") (pin "15") (pinfunction "GPIO14(USART1_RX)_15") (pintype "bidirectional"))
      (node (ref "U1") (pin "B15") (pinfunction "GPIO14(USART1_RX)_B15") (pintype "bidirectional"))
    )
    (net (code "22") (name "EXPRESSION_IN") (class "Default")
      (node (ref "U1") (pin "22") (pinfunction "GPIO15(ADC0)_22") (pintype "bidirectional"))
      (node (ref "U1") (pin "B22") (pinfunction "GPIO15(ADC0)_B22") (pintype "bidirectional"))
      (node (ref "U8") (pin "13") (pinfunction "-IN_13") (pintype "input"))
      (node (ref "U8") (pin "14") (pinfunction "OUT_14") (pintype "output"))
    )
    (net (code "23") (name "EXPRESSION_IN_EXT") (class "Default")
      (node (ref "P1") (pin "15") (pinfunction "15_15") (pintype "passive"))
      (node (ref "R5") (pin "2") (pinfunction "2_2") (pintype "passive"))
      (node (ref "U8") (pin "12") (pinfunction "+IN_12") (pintype "input"))
    )
    (net (code "24") (name "EXPRESSION_IN_JACK") (class "Default")
      (node (ref "J10") (pin "2") (pinfunction "TIP_2") (pintype "passive"))
      (node (ref "P8") (pin "2") (pinfunction "2_2") (pintype "passive"))
    )
    (net (code "25") (name "EXPRESSION_REF") (class "Default")
      (node (ref "P1") (pin "16") (pinfunction "16_16") (pintype "passive"))
      (node (ref "U8") (pin "8") (pinfunction "OUT_8") (pintype "output"))
      (node (ref "U8") (pin "9") (pinfunction "-IN_9") (pintype "input"))
    )
    (net (code "26") (name "EXPRESSION_REF_JACK") (class "Default")
      (node (ref "J10") (pin "3") (pinfunction "RING_3") (pintype "passive"))
      (node (ref "P8") (pin "1") (pinfunction "1_1") (pintype "passive"))
    )
    (net (code "27") (name "FOOTSWITCH_1") (class "Default")
      (node (ref "SV1") (pin "1") (pinfunction "S_1") (pintype "passive"))
      (node (ref "U1") (pin "9") (pinfunction "GPIO8(SPI1_SCK)_9") (pintype "bidirectional"))
      (node (ref "U1") (pin "B9") (pinfunction "GPIO8(SPI1_SCK)_B9") (pintype "bidirectional"))
    )
    (net (code "28") (name "FOOTSWITCH_2") (class "Default")
      (node (ref "SV2") (pin "1") (pinfunction "S_1") (pintype "passive"))
      (node (ref "U1") (pin "10") (pinfunction "GPIO9(SPI1_MISO)_10") (pintype "bidirectional"))
      (node (ref "U1") (pin "B10") (pinfunction "GPIO9(SPI1_MISO)_B10") (pintype "bidirectional"))
    )
    (net (code "29") (name "FOOTSWITCH_3") (class "Default")
      (node (ref "SV3") (pin "1") (pinfunction "S_1") (pintype "passive"))
      (node (ref "U1") (pin "11") (pinfunction "GPIO10(SPI1_MOSI)_11") (pintype "bidirectional"))
      (node (ref "U1") (pin "B11") (pinfunction "GPIO10(SPI1_MOSI)_B11") (pintype "bidirectional"))
    )
    (net (code "30") (name "FOOTSWITCH_4") (class "Default")
      (node (ref "SV4") (pin "1") (pinfunction "S_1") (pintype "passive"))
      (node (ref "U1") (pin "14") (pinfunction "GPIO13(USART1_TX)_14") (pintype "bidirectional"))
      (node (ref "U1") (pin "B14") (pinfunction "GPIO13(USART1_TX)_B14") (pintype "bidirectional"))
    )
    (net (code "31") (name "GND") (class "Default")
      (node (ref "C13") (pin "2") (pinfunction "2_2") (pintype "passive"))
      (node (ref "C14") (pin "2") (pinfunction "2_2") (pintype "passive"))
      (node (ref "C16") (pin "2") (pinfunction "2_2") (pintype "passive"))
      (node (ref "C2") (pin "2") (pinfunction "2_2") (pintype "passive"))
      (node (ref "C3") (pin "2") (pinfunction "2_2") (pintype "passive"))
      (node (ref "C4") (pin "1") (pinfunction "1_1") (pintype "passive"))
      (node (ref "C5") (pin "1") (pinfunction "1_1") (pintype "passive"))
      (node (ref "C6") (pin "2") (pinfunction "2_2") (pintype "passive"))
      (node (ref "C7") (pin "2") (pinfunction "2_2") (pintype "passive"))
      (node (ref "C8") (pin "2") (pinfunction "2_2") (pintype "passive"))
      (node (ref "ENC_1") (pin "C") (pinfunction "C_C") (pintype "passive"))
      (node (ref "ENC_1") (pin "D") (pinfunction "1_D") (pintype "passive"))
      (node (ref "G1") (pin "-") (pinfunction "-_-") (pintype "passive"))
      (node (ref "H1") (pin "B3,2") (pinfunction "MOUNT_B3,2") (pintype "passive"))
      (node (ref "J10") (pin "1") (pinfunction "SLEEVE_1") (pintype "passive"))
      (node (ref "J10") (pin "4") (pinfunction "SLEEVE_SW_4") (pintype "passive"))
      (node (ref "J12") (pin "1") (pinfunction "SLEEVE_1") (pintype "passive"))
      (node (ref "J12") (pin "4") (pinfunction "SLEEVE_SW_4") (pintype "passive"))
      (node (ref "J13") (pin "1") (pinfunction "SLEEVE_1") (pintype "passive"))
      (node (ref "J13") (pin "4") (pinfunction "SLEEVE_SW_4") (pintype "passive"))
      (node (ref "J7") (pin "1") (pinfunction "GND_1") (pintype "passive"))
      (node (ref "J7") (pin "4") (pinfunction "GND_4") (pintype "passive"))
      (node (ref "J8") (pin "1") (pinfunction "SLEEVE_1") (pintype "passive"))
      (node (ref "J8") (pin "4") (pinfunction "SLEEVE_SW_4") (pintype "passive"))
      (node (ref "J9") (pin "1") (pinfunction "SLEEVE_1") (pintype "passive"))
      (node (ref "J9") (pin "4") (pinfunction "SLEEVE_SW_4") (pintype "passive"))
      (node (ref "P1") (pin "1") (pinfunction "1_1") (pintype "passive"))
      (node (ref "P1") (pin "13") (pinfunction "13_13") (pintype "passive"))
      (node (ref "P1") (pin "14") (pinfunction "14_14") (pintype "passive"))
      (node (ref "P1") (pin "2") (pinfunction "2_2") (pintype "passive"))
      (node (ref "P1") (pin "3") (pinfunction "3_3") (pintype "passive"))
      (node (ref "P1") (pin "4") (pinfunction "4_4") (pintype "passive"))
      (node (ref "P8") (pin "13") (pinfunction "13_13") (pintype "passive"))
      (node (ref "P8") (pin "14") (pinfunction "14_14") (pintype "passive"))
      (node (ref "P8") (pin "15") (pinfunction "15_15") (pintype "passive"))
      (node (ref "P8") (pin "16") (pinfunction "16_16") (pintype "passive"))
      (node (ref "P8") (pin "3") (pinfunction "3_3") (pintype "passive"))
      (node (ref "P8") (pin "4") (pinfunction "4_4") (pintype "passive"))
      (node (ref "R31") (pin "1") (pinfunction "1_1") (pintype "passive"))
      (node (ref "R32") (pin "1") (pinfunction "1_1") (pintype "passive"))
      (node (ref "R34") (pin "1") (pinfunction "1_1") (pintype "passive"))
      (node (ref "R35") (pin "1") (pinfunction "1_1") (pintype "passive"))
      (node (ref "R37") (pin "1") (pinfunction "1_1") (pintype "passive"))
      (node (ref "R39") (pin "1") (pinfunction "1_1") (pintype "passive"))
      (node (ref "R40") (pin "1") (pinfunction "1_1") (pintype "passive"))
      (node (ref "R5") (pin "1") (pinfunction "1_1") (pintype "passive"))
      (node (ref "SV1") (pin "2") (pinfunction "S_2") (pintype "passive"))
      (node (ref "SV2") (pin "2") (pinfunction "S_2") (pintype "passive"))
      (node (ref "SV3") (pin "2") (pinfunction "S_2") (pintype "passive"))
      (node (ref "SV4") (pin "2") (pinfunction "S_2") (pintype "passive"))
      (node (ref "SW_5") (pin "1") (pinfunction "O_1") (pintype "passive"))
      (node (ref "SW_6") (pin "1") (pinfunction "O_1") (pintype "passive"))
      (node (ref "SW_7") (pin "1") (pinfunction "O_1") (pintype "passive"))
      (node (ref "U$3") (pin "P$1") (pinfunction "IN-_P$1") (pintype "bidirectional"))
      (node (ref "U$3") (pin "P$4") (pinfunction "OUT-_P$4") (pintype "bidirectional"))
      (node (ref "U1") (pin "20") (pinfunction "AGND_20") (pintype "bidirectional"))
      (node (ref "U1") (pin "40") (pinfunction "GND_40") (pintype "bidirectional"))
      (node (ref "U1") (pin "B20") (pinfunction "AGND_B20") (pintype "bidirectional"))
      (node (ref "U1") (pin "B40") (pinfunction "GND_B40") (pintype "bidirectional"))
      (node (ref "U2") (pin "GND1") (pinfunction "SHIELD_GND1") (pintype "bidirectional"))
      (node (ref "U2") (pin "GND2") (pinfunction "SHIELD_GND2") (pintype "bidirectional"))
      (node (ref "U2") (pin "P$6") (pinfunction "GND_P$6") (pintype "bidirectional"))
      (node (ref "U3") (pin "14") (pinfunction "GND_14") (pintype "power_in"))
      (node (ref "U3") (pin "2") (pinfunction "A1_2") (pintype "bidirectional"))
      (node (ref "U3") (pin "23") (pinfunction "/OE_23") (pintype "bidirectional"))
      (node (ref "U3") (pin "24") (pinfunction "A5_24") (pintype "bidirectional"))
      (node (ref "U3") (pin "25") (pinfunction "EXTCLK_25") (pintype "input"))
      (node (ref "U3") (pin "3") (pinfunction "A2_3") (pintype "bidirectional"))
      (node (ref "U3") (pin "4") (pinfunction "A3_4") (pintype "bidirectional"))
      (node (ref "U3") (pin "5") (pinfunction "A4_5") (pintype "bidirectional"))
      (node (ref "U4") (pin "1") (pinfunction "A0_1") (pintype "bidirectional"))
      (node (ref "U4") (pin "14") (pinfunction "GND_14") (pintype "power_in"))
      (node (ref "U4") (pin "2") (pinfunction "A1_2") (pintype "bidirectional"))
      (node (ref "U4") (pin "23") (pinfunction "/OE_23") (pintype "bidirectional"))
      (node (ref "U4") (pin "24") (pinfunction "A5_24") (pintype "bidirectional"))
      (node (ref "U4") (pin "25") (pinfunction "EXTCLK_25") (pintype "input"))
      (node (ref "U4") (pin "3") (pinfunction "A2_3") (pintype "bidirectional"))
      (node (ref "U4") (pin "4") (pinfunction "A3_4") (pintype "bidirectional"))
      (node (ref "U4") (pin "5") (pinfunction "A4_5") (pintype "bidirectional"))
      (node (ref "U5") (pin "1") (pinfunction "GND_1") (pintype "input"))
      (node (ref "U6") (pin "10") (pinfunction "+IN_10") (pintype "input"))
      (node (ref "U6") (pin "11") (pinfunction "V-_11") (pintype "power_in"))
      (node (ref "U8") (pin "11") (pinfunction "V-_11") (pintype "power_in"))
      (node (ref "VR_1") (pin "1") (pinfunction "A_1") (pintype "passive"))
      (node (ref "VR_1") (pin "CHASSIS1") (pinfunction "CHASSIS_CHASSIS1") (pintype "passive"))
      (node (ref "VR_1") (pin "CHASSIS2") (pinfunction "CHASSIS_CHASSIS2") (pintype "passive"))
      (node (ref "VR_2") (pin "1") (pinfunction "A_1") (pintype "passive"))
      (node (ref "VR_2") (pin "CHASSIS1") (pinfunction "CHASSIS_CHASSIS1") (pintype "passive"))
      (node (ref "VR_2") (pin "CHASSIS2") (pinfunction "CHASSIS_CHASSIS2") (pintype "passive"))
      (node (ref "VR_3") (pin "1") (pinfunction "A_1") (pintype "passive"))
      (node (ref "VR_3") (pin "CHASSIS1") (pinfunction "CHASSIS_CHASSIS1") (pintype "passive"))
      (node (ref "VR_3") (pin "CHASSIS2") (pinfunction "CHASSIS_CHASSIS2") (pintype "passive"))
      (node (ref "VR_4") (pin "1") (pinfunction "A_1") (pintype "passive"))
      (node (ref "VR_4") (pin "CHASSIS1") (pinfunction "CHASSIS_CHASSIS1") (pintype "passive"))
      (node (ref "VR_4") (pin "CHASSIS2") (pinfunction "CHASSIS_CHASSIS2") (pintype "passive"))
      (node (ref "VR_5") (pin "1") (pinfunction "A_1") (pintype "passive"))
      (node (ref "VR_5") (pin "CHASSIS1") (pinfunction "CHASSIS_CHASSIS1") (pintype "passive"))
      (node (ref "VR_5") (pin "CHASSIS2") (pinfunction "CHASSIS_CHASSIS2") (pintype "passive"))
      (node (ref "VR_6") (pin "1") (pinfunction "A_1") (pintype "passive"))
      (node (ref "VR_6") (pin "CHASSIS1") (pinfunction "CHASSIS_CHASSIS1") (pintype "passive"))
      (node (ref "VR_6") (pin "CHASSIS2") (pinfunction "CHASSIS_CHASSIS2") (pintype "passive"))
    )
    (net (code "32") (name "GPIO23") (class "Default")
      (node (ref "U1") (pin "29") (pinfunction "GPIO22(ADC7/DAC2)_29") (pintype "bidirectional"))
      (node (ref "U1") (pin "B29") (pinfunction "GPIO22(ADC7/DAC2)_B29") (pintype "bidirectional"))
    )
    (net (code "33") (name "GPIO24") (class "Default")
      (node (ref "U1") (pin "30") (pinfunction "GPIO23(ADC8/DAC1)_30") (pintype "bidirectional"))
      (node (ref "U1") (pin "B30") (pinfunction "GPIO23(ADC8/DAC1)_B30") (pintype "bidirectional"))
    )
    (net (code "34") (name "GPIO25") (class "Default")
      (node (ref "U1") (pin "31") (pinfunction "GPIO24(ADC9)_31") (pintype "bidirectional"))
      (node (ref "U1") (pin "B31") (pinfunction "GPIO24(ADC9)_B31") (pintype "bidirectional"))
    )
    (net (code "35") (name "I2C1_SCL") (class "Default")
      (node (ref "R29") (pin "1") (pinfunction "1_1") (pintype "passive"))
      (node (ref "U1") (pin "12") (pinfunction "GPIO11(I2C1_SCL)_12") (pintype "bidirectional"))
      (node (ref "U1") (pin "B12") (pinfunction "GPIO11(I2C1_SCL)_B12") (pintype "bidirectional"))
      (node (ref "U3") (pin "26") (pinfunction "SCL_26") (pintype "bidirectional"))
      (node (ref "U4") (pin "26") (pinfunction "SCL_26") (pintype "bidirectional"))
    )
    (net (code "36") (name "I2C1_SDA") (class "Default")
      (node (ref "R28") (pin "1") (pinfunction "1_1") (pintype "passive"))
      (node (ref "U1") (pin "13") (pinfunction "GPIO12(I2C1_SDA)_13") (pintype "bidirectional"))
      (node (ref "U1") (pin "B13") (pinfunction "GPIO12(I2C1_SDA)_B13") (pintype "bidirectional"))
      (node (ref "U3") (pin "27") (pinfunction "SDA_27") (pintype "bidirectional"))
      (node (ref "U4") (pin "27") (pinfunction "SDA_27") (pintype "bidirectional"))
    )
    (net (code "37") (name "Net-(C10-Pad1)") (class "Default")
      (node (ref "C10") (pin "1") (pinfunction "1_1") (pintype "passive"))
      (node (ref "R42") (pin "1") (pinfunction "1_1") (pintype "passive"))
    )
    (net (code "38") (name "Net-(C12-Pad1)") (class "Default")
      (node (ref "C12") (pin "1") (pinfunction "1_1") (pintype "passive"))
      (node (ref "R43") (pin "1") (pinfunction "1_1") (pintype "passive"))
    )
    (net (code "39") (name "Net-(J7-PIN)") (class "Default")
      (node (ref "D1") (pin "A") (pinfunction "A_A") (pintype "passive"))
      (node (ref "J7") (pin "3") (pinfunction "PIN_3") (pintype "passive"))
    )
    (net (code "40") (name "Net-(J9-TIP_SW)") (class "Default")
      (node (ref "J9") (pin "5") (pinfunction "TIP_SW_5") (pintype "passive"))
      (node (ref "R44") (pin "2") (pinfunction "2_2") (pintype "passive"))
    )
    (net (code "41") (name "Net-(LED_RING_1-B)") (class "Default")
      (node (ref "LED_RING_1") (pin "3") (pinfunction "B_3") (pintype "bidirectional"))
      (node (ref "R8") (pin "2") (pinfunction "2_2") (pintype "passive"))
    )
    (net (code "42") (name "Net-(LED_RING_1-G)") (class "Default")
      (node (ref "LED_RING_1") (pin "4") (pinfunction "G_4") (pintype "bidirectional"))
      (node (ref "R6") (pin "2") (pinfunction "2_2") (pintype "passive"))
    )
    (net (code "43") (name "Net-(LED_RING_1-R)") (class "Default")
      (node (ref "LED_RING_1") (pin "1") (pinfunction "R_1") (pintype "bidirectional"))
      (node (ref "R7") (pin "2") (pinfunction "2_2") (pintype "passive"))
    )
    (net (code "44") (name "Net-(LED_RING_2-B)") (class "Default")
      (node (ref "LED_RING_2") (pin "3") (pinfunction "B_3") (pintype "bidirectional"))
      (node (ref "R19") (pin "2") (pinfunction "2_2") (pintype "passive"))
    )
    (net (code "45") (name "Net-(LED_RING_2-G)") (class "Default")
      (node (ref "LED_RING_2") (pin "4") (pinfunction "G_4") (pintype "bidirectional"))
      (node (ref "R18") (pin "2") (pinfunction "2_2") (pintype "passive"))
    )
    (net (code "46") (name "Net-(LED_RING_2-R)") (class "Default")
      (node (ref "LED_RING_2") (pin "1") (pinfunction "R_1") (pintype "bidirectional"))
      (node (ref "R17") (pin "2") (pinfunction "2_2") (pintype "passive"))
    )
    (net (code "47") (name "Net-(LED_RING_3-B)") (class "Default")
      (node (ref "LED_RING_3") (pin "3") (pinfunction "B_3") (pintype "bidirectional"))
      (node (ref "R25") (pin "2") (pinfunction "2_2") (pintype "passive"))
    )
    (net (code "48") (name "Net-(LED_RING_3-G)") (class "Default")
      (node (ref "LED_RING_3") (pin "4") (pinfunction "G_4") (pintype "bidirectional"))
      (node (ref "R24") (pin "2") (pinfunction "2_2") (pintype "passive"))
    )
    (net (code "49") (name "Net-(LED_RING_3-R)") (class "Default")
      (node (ref "LED_RING_3") (pin "1") (pinfunction "R_1") (pintype "bidirectional"))
      (node (ref "R23") (pin "2") (pinfunction "2_2") (pintype "passive"))
    )
    (net (code "50") (name "Net-(LED_RING_4-B)") (class "Default")
      (node (ref "LED_RING_4") (pin "3") (pinfunction "B_3") (pintype "bidirectional"))
      (node (ref "R50") (pin "2") (pinfunction "2_2") (pintype "passive"))
    )
    (net (code "51") (name "Net-(LED_RING_4-G)") (class "Default")
      (node (ref "LED_RING_4") (pin "4") (pinfunction "G_4") (pintype "bidirectional"))
      (node (ref "R27") (pin "2") (pinfunction "2_2") (pintype "passive"))
    )
    (net (code "52") (name "Net-(LED_RING_4-R)") (class "Default")
      (node (ref "LED_RING_4") (pin "1") (pinfunction "R_1") (pintype "bidirectional"))
      (node (ref "R26") (pin "2") (pinfunction "2_2") (pintype "passive"))
    )
    (net (code "53") (name "Net-(LED_RING_5-B)") (class "Default")
      (node (ref "LED_RING_5") (pin "3") (pinfunction "B_3") (pintype "bidirectional"))
      (node (ref "R11") (pin "2") (pinfunction "2_2") (pintype "passive"))
    )
    (net (code "54") (name "Net-(LED_RING_5-G)") (class "Default")
      (node (ref "LED_RING_5") (pin "4") (pinfunction "G_4") (pintype "bidirectional"))
      (node (ref "R10") (pin "2") (pinfunction "2_2") (pintype "passive"))
    )
    (net (code "55") (name "Net-(LED_RING_5-R)") (class "Default")
      (node (ref "LED_RING_5") (pin "1") (pinfunction "R_1") (pintype "bidirectional"))
      (node (ref "R9") (pin "2") (pinfunction "2_2") (pintype "passive"))
    )
    (net (code "56") (name "Net-(LED_RING_6-B)") (class "Default")
      (node (ref "LED_RING_6") (pin "3") (pinfunction "B_3") (pintype "bidirectional"))
      (node (ref "R22") (pin "2") (pinfunction "2_2") (pintype "passive"))
    )
    (net (code "57") (name "Net-(LED_RING_6-G)") (class "Default")
      (node (ref "LED_RING_6") (pin "4") (pinfunction "G_4") (pintype "bidirectional"))
      (node (ref "R21") (pin "2") (pinfunction "2_2") (pintype "passive"))
    )
    (net (code "58") (name "Net-(LED_RING_6-R)") (class "Default")
      (node (ref "LED_RING_6") (pin "1") (pinfunction "R_1") (pintype "bidirectional"))
      (node (ref "R20") (pin "2") (pinfunction "2_2") (pintype "passive"))
    )
    (net (code "59") (name "Net-(LED_RING_7-B)") (class "Default")
      (node (ref "LED_RING_7") (pin "3") (pinfunction "B_3") (pintype "bidirectional"))
      (node (ref "R53") (pin "2") (pinfunction "2_2") (pintype "passive"))
    )
    (net (code "60") (name "Net-(LED_RING_7-G)") (class "Default")
      (node (ref "LED_RING_7") (pin "4") (pinfunction "G_4") (pintype "bidirectional"))
      (node (ref "R52") (pin "2") (pinfunction "2_2") (pintype "passive"))
    )
    (net (code "61") (name "Net-(LED_RING_7-R)") (class "Default")
      (node (ref "LED_RING_7") (pin "1") (pinfunction "R_1") (pintype "bidirectional"))
      (node (ref "R51") (pin "2") (pinfunction "2_2") (pintype "passive"))
    )
    (net (code "62") (name "Net-(LED_RING_8-B)") (class "Default")
      (node (ref "LED_RING_8") (pin "3") (pinfunction "B_3") (pintype "bidirectional"))
      (node (ref "R56") (pin "2") (pinfunction "2_2") (pintype "passive"))
    )
    (net (code "63") (name "Net-(LED_RING_8-G)") (class "Default")
      (node (ref "LED_RING_8") (pin "4") (pinfunction "G_4") (pintype "bidirectional"))
      (node (ref "R55") (pin "2") (pinfunction "2_2") (pintype "passive"))
    )
    (net (code "64") (name "Net-(LED_RING_8-R)") (class "Default")
      (node (ref "LED_RING_8") (pin "1") (pinfunction "R_1") (pintype "bidirectional"))
      (node (ref "R54") (pin "2") (pinfunction "2_2") (pintype "passive"))
    )
    (net (code "65") (name "Net-(LED_SW_1-A)") (class "Default")
      (node (ref "LED_SW_1") (pin "ANODE") (pinfunction "A_ANODE") (pintype "passive"))
      (node (ref "R12") (pin "1") (pinfunction "1_1") (pintype "passive"))
    )
    (net (code "66") (name "Net-(LED_SW_1-C)") (class "Default")
      (node (ref "LED_SW_1") (pin "CATHODE") (pinfunction "C_CATHODE") (pintype "passive"))
      (node (ref "U4") (pin "22") (pinfunction "LED15_22") (pintype "bidirectional"))
    )
    (net (code "67") (name "Net-(LED_SW_2-A)") (class "Default")
      (node (ref "LED_SW_2") (pin "ANODE") (pinfunction "A_ANODE") (pintype "passive"))
      (node (ref "R13") (pin "1") (pinfunction "1_1") (pintype "passive"))
    )
    (net (code "68") (name "Net-(LED_SW_2-C)") (class "Default")
      (node (ref "LED_SW_2") (pin "CATHODE") (pinfunction "C_CATHODE") (pintype "passive"))
      (node (ref "U3") (pin "16") (pinfunction "LED9_16") (pintype "bidirectional"))
    )
    (net (code "69") (name "Net-(LED_SW_3-A)") (class "Default")
      (node (ref "LED_SW_3") (pin "ANODE") (pinfunction "A_ANODE") (pintype "passive"))
      (node (ref "R14") (pin "1") (pinfunction "1_1") (pintype "passive"))
    )
    (net (code "70") (name "Net-(LED_SW_3-C)") (class "Default")
      (node (ref "LED_SW_3") (pin "CATHODE") (pinfunction "C_CATHODE") (pintype "passive"))
      (node (ref "U3") (pin "17") (pinfunction "LED10_17") (pintype "bidirectional"))
    )
    (net (code "71") (name "Net-(LED_SW_4-A)") (class "Default")
      (node (ref "LED_SW_4") (pin "ANODE") (pinfunction "A_ANODE") (pintype "passive"))
      (node (ref "R15") (pin "1") (pinfunction "1_1") (pintype "passive"))
    )
    (net (code "72") (name "Net-(LED_SW_4-C)") (class "Default")
      (node (ref "LED_SW_4") (pin "CATHODE") (pinfunction "C_CATHODE") (pintype "passive"))
      (node (ref "U3") (pin "18") (pinfunction "LED11_18") (pintype "bidirectional"))
    )
    (net (code "73") (name "Net-(U$3-IN+)") (class "Default")
      (node (ref "C7") (pin "1") (pinfunction "1_1") (pintype "passive"))
      (node (ref "L1") (pin "P$2") (pinfunction "P$2_P$2") (pintype "bidirectional"))
      (node (ref "U$3") (pin "P$2") (pinfunction "IN+_P$2") (pintype "bidirectional"))
    )
    (net (code "74") (name "Net-(U3-LED0)") (class "Default")
      (node (ref "R26") (pin "1") (pinfunction "1_1") (pintype "passive"))
      (node (ref "U3") (pin "6") (pinfunction "LED0_6") (pintype "bidirectional"))
    )
    (net (code "75") (name "Net-(U3-LED1)") (class "Default")
      (node (ref "R27") (pin "1") (pinfunction "1_1") (pintype "passive"))
      (node (ref "U3") (pin "7") (pinfunction "LED1_7") (pintype "bidirectional"))
    )
    (net (code "76") (name "Net-(U3-LED2)") (class "Default")
      (node (ref "R50") (pin "1") (pinfunction "1_1") (pintype "passive"))
      (node (ref "U3") (pin "8") (pinfunction "LED2_8") (pintype "bidirectional"))
    )
    (net (code "77") (name "Net-(U3-LED3)") (class "Default")
      (node (ref "R51") (pin "1") (pinfunction "1_1") (pintype "passive"))
      (node (ref "U3") (pin "9") (pinfunction "LED3_9") (pintype "bidirectional"))
    )
    (net (code "78") (name "Net-(U3-LED4)") (class "Default")
      (node (ref "R52") (pin "1") (pinfunction "1_1") (pintype "passive"))
      (node (ref "U3") (pin "10") (pinfunction "LED4_10") (pintype "bidirectional"))
    )
    (net (code "79") (name "Net-(U3-LED5)") (class "Default")
      (node (ref "R53") (pin "1") (pinfunction "1_1") (pintype "passive"))
      (node (ref "U3") (pin "11") (pinfunction "LED5_11") (pintype "bidirectional"))
    )
    (net (code "80") (name "Net-(U3-LED6)") (class "Default")
      (node (ref "R54") (pin "1") (pinfunction "1_1") (pintype "passive"))
      (node (ref "U3") (pin "12") (pinfunction "LED6_12") (pintype "bidirectional"))
    )
    (net (code "81") (name "Net-(U3-LED7)") (class "Default")
      (node (ref "R55") (pin "1") (pinfunction "1_1") (pintype "passive"))
      (node (ref "U3") (pin "13") (pinfunction "LED7_13") (pintype "bidirectional"))
    )
    (net (code "82") (name "Net-(U3-LED8)") (class "Default")
      (node (ref "R56") (pin "1") (pinfunction "1_1") (pintype "passive"))
      (node (ref "U3") (pin "15") (pinfunction "LED8_15") (pintype "bidirectional"))
    )
    (net (code "83") (name "Net-(U4-LED0)") (class "Default")
      (node (ref "R7") (pin "1") (pinfunction "1_1") (pintype "passive"))
      (node (ref "U4") (pin "6") (pinfunction "LED0_6") (pintype "bidirectional"))
    )
    (net (code "84") (name "Net-(U4-LED1)") (class "Default")
      (node (ref "R6") (pin "1") (pinfunction "1_1") (pintype "passive"))
      (node (ref "U4") (pin "7") (pinfunction "LED1_7") (pintype "bidirectional"))
    )
    (net (code "85") (name "Net-(U4-LED2)") (class "Default")
      (node (ref "R8") (pin "1") (pinfunction "1_1") (pintype "passive"))
      (node (ref "U4") (pin "8") (pinfunction "LED2_8") (pintype "bidirectional"))
    )
    (net (code "86") (name "Net-(U4-LED3)") (class "Default")
      (node (ref "R9") (pin "1") (pinfunction "1_1") (pintype "passive"))
      (node (ref "U4") (pin "9") (pinfunction "LED3_9") (pintype "bidirectional"))
    )
    (net (code "87") (name "Net-(U4-LED4)") (class "Default")
      (node (ref "R10") (pin "1") (pinfunction "1_1") (pintype "passive"))
      (node (ref "U4") (pin "10") (pinfunction "LED4_10") (pintype "bidirectional"))
    )
    (net (code "88") (name "Net-(U4-LED5)") (class "Default")
      (node (ref "R11") (pin "1") (pinfunction "1_1") (pintype "passive"))
      (node (ref "U4") (pin "11") (pinfunction "LED5_11") (pintype "bidirectional"))
    )
    (net (code "89") (name "Net-(U4-LED6)") (class "Default")
      (node (ref "R17") (pin "1") (pinfunction "1_1") (pintype "passive"))
      (node (ref "U4") (pin "12") (pinfunction "LED6_12") (pintype "bidirectional"))
    )
    (net (code "90") (name "Net-(U4-LED7)") (class "Default")
      (node (ref "R18") (pin "1") (pinfunction "1_1") (pintype "passive"))
      (node (ref "U4") (pin "13") (pinfunction "LED7_13") (pintype "bidirectional"))
    )
    (net (code "91") (name "Net-(U4-LED8)") (class "Default")
      (node (ref "R19") (pin "1") (pinfunction "1_1") (pintype "passive"))
      (node (ref "U4") (pin "15") (pinfunction "LED8_15") (pintype "bidirectional"))
    )
    (net (code "92") (name "Net-(U4-LED9)") (class "Default")
      (node (ref "R20") (pin "1") (pinfunction "1_1") (pintype "passive"))
      (node (ref "U4") (pin "16") (pinfunction "LED9_16") (pintype "bidirectional"))
    )
    (net (code "93") (name "Net-(U4-LED10)") (class "Default")
      (node (ref "R21") (pin "1") (pinfunction "1_1") (pintype "passive"))
      (node (ref "U4") (pin "17") (pinfunction "LED10_17") (pintype "bidirectional"))
    )
    (net (code "94") (name "Net-(U4-LED11)") (class "Default")
      (node (ref "R22") (pin "1") (pinfunction "1_1") (pintype "passive"))
      (node (ref "U4") (pin "18") (pinfunction "LED11_18") (pintype "bidirectional"))
    )
    (net (code "95") (name "Net-(U4-LED12)") (class "Default")
      (node (ref "R23") (pin "1") (pinfunction "1_1") (pintype "passive"))
      (node (ref "U4") (pin "19") (pinfunction "LED12_19") (pintype "bidirectional"))
    )
    (net (code "96") (name "Net-(U4-LED13)") (class "Default")
      (node (ref "R24") (pin "1") (pinfunction "1_1") (pintype "passive"))
      (node (ref "U4") (pin "20") (pinfunction "LED13_20") (pintype "bidirectional"))
    )
    (net (code "97") (name "Net-(U4-LED14)") (class "Default")
      (node (ref "R25") (pin "1") (pinfunction "1_1") (pintype "passive"))
      (node (ref "U4") (pin "21") (pinfunction "LED14_21") (pintype "bidirectional"))
    )
    (net (code "98") (name "Net-(U6A-+IN)") (class "Default")
      (node (ref "C15") (pin "2") (pinfunction "2_2") (pintype "passive"))
      (node (ref "R38") (pin "1") (pinfunction "1_1") (pintype "passive"))
      (node (ref "U6") (pin "3") (pinfunction "+IN_3") (pintype "input"))
    )
    (net (code "99") (name "Net-(U6B-+IN)") (class "Default")
      (node (ref "C1") (pin "2") (pinfunction "2_2") (pintype "passive"))
      (node (ref "R36") (pin "1") (pinfunction "1_1") (pintype "passive"))
      (node (ref "U6") (pin "5") (pinfunction "+IN_5") (pintype "input"))
    )
    (net (code "100") (name "Net-(U6C--IN)") (class "Default")
      (node (ref "U6") (pin "8") (pinfunction "OUT_8") (pintype "output"))
      (node (ref "U6") (pin "9") (pinfunction "-IN_9") (pintype "input"))
    )
    (net (code "101") (name "Net-(U6D-+IN)") (class "Default")
      (node (ref "R40") (pin "2") (pinfunction "2_2") (pintype "passive"))
      (node (ref "R41") (pin "1") (pinfunction "1_1") (pintype "passive"))
      (node (ref "U6") (pin "12") (pinfunction "+IN_12") (pintype "input"))
    )
    (net (code "102") (name "Net-(U8A-+IN)") (class "Default")
      (node (ref "C9") (pin "2") (pinfunction "2_2") (pintype "passive"))
      (node (ref "R30") (pin "1") (pinfunction "1_1") (pintype "passive"))
      (node (ref "R31") (pin "2") (pinfunction "2_2") (pintype "passive"))
      (node (ref "U8") (pin "3") (pinfunction "+IN_3") (pintype "input"))
    )
    (net (code "103") (name "Net-(U8A--IN)") (class "Default")
      (node (ref "R42") (pin "2") (pinfunction "2_2") (pintype "passive"))
      (node (ref "U8") (pin "1") (pinfunction "OUT_1") (pintype "output"))
      (node (ref "U8") (pin "2") (pinfunction "-IN_2") (pintype "input"))
    )
    (net (code "104") (name "Net-(U8B-+IN)") (class "Default")
      (node (ref "C11") (pin "2") (pinfunction "2_2") (pintype "passive"))
      (node (ref "R33") (pin "1") (pinfunction "1_1") (pintype "passive"))
      (node (ref "R34") (pin "2") (pinfunction "2_2") (pintype "passive"))
      (node (ref "U8") (pin "5") (pinfunction "+IN_5") (pintype "input"))
    )
    (net (code "105") (name "Net-(U8B--IN)") (class "Default")
      (node (ref "R43") (pin "2") (pinfunction "2_2") (pintype "passive"))
      (node (ref "U8") (pin "6") (pinfunction "-IN_6") (pintype "input"))
      (node (ref "U8") (pin "7") (pinfunction "OUT_7") (pintype "output"))
    )
    (net (code "106") (name "POT_1") (class "Default")
      (node (ref "U1") (pin "23") (pinfunction "GPIO16(ADC1)_23") (pintype "bidirectional"))
      (node (ref "U1") (pin "B23") (pinfunction "GPIO16(ADC1)_B23") (pintype "bidirectional"))
      (node (ref "VR_1") (pin "2") (pinfunction "S_2") (pintype "passive"))
    )
    (net (code "107") (name "POT_2") (class "Default")
      (node (ref "U1") (pin "26") (pinfunction "GPIO19(ADC4)_26") (pintype "bidirectional"))
      (node (ref "U1") (pin "B26") (pinfunction "GPIO19(ADC4)_B26") (pintype "bidirectional"))
      (node (ref "VR_2") (pin "2") (pinfunction "S_2") (pintype "passive"))
    )
    (net (code "108") (name "POT_3") (class "Default")
      (node (ref "U1") (pin "24") (pinfunction "GPIO17(ADC2)_24") (pintype "bidirectional"))
      (node (ref "U1") (pin "B24") (pinfunction "GPIO17(ADC2)_B24") (pintype "bidirectional"))
      (node (ref "VR_3") (pin "2") (pinfunction "S_2") (pintype "passive"))
    )
    (net (code "109") (name "POT_4") (class "Default")
      (node (ref "U1") (pin "27") (pinfunction "GPIO20(ADC5)_27") (pintype "bidirectional"))
      (node (ref "U1") (pin "B27") (pinfunction "GPIO20(ADC5)_B27") (pintype "bidirectional"))
      (node (ref "VR_4") (pin "2") (pinfunction "S_2") (pintype "passive"))
    )
    (net (code "110") (name "POT_5") (class "Default")
      (node (ref "U1") (pin "25") (pinfunction "GPIO18(ADC3)_25") (pintype "bidirectional"))
      (node (ref "U1") (pin "B25") (pinfunction "GPIO18(ADC3)_B25") (pintype "bidirectional"))
      (node (ref "VR_5") (pin "2") (pinfunction "S_2") (pintype "passive"))
    )
    (net (code "111") (name "POT_6") (class "Default")
      (node (ref "U1") (pin "28") (pinfunction "GPIO21(ADC6)_28") (pintype "bidirectional"))
      (node (ref "U1") (pin "B28") (pinfunction "GPIO21(ADC6)_B28") (pintype "bidirectional"))
      (node (ref "VR_6") (pin "2") (pinfunction "S_2") (pintype "passive"))
    )
    (net (code "112") (name "SD_CK") (class "Default")
      (node (ref "U1") (pin "7") (pinfunction "GPIO6(SDMMC1_CK)_7") (pintype "bidirectional"))
      (node (ref "U1") (pin "B7") (pinfunction "GPIO6(SDMMC1_CK)_B7") (pintype "bidirectional"))
      (node (ref "U2") (pin "P$5") (pinfunction "SCK_P$5") (pintype "bidirectional"))
    )
    (net (code "113") (name "SD_CMD") (class "Default")
      (node (ref "R1") (pin "1") (pinfunction "1_1") (pintype "passive"))
      (node (ref "U1") (pin "6") (pinfunction "GPIO5(SDMMC1_CMD)_6") (pintype "bidirectional"))
      (node (ref "U1") (pin "B6") (pinfunction "GPIO5(SDMMC1_CMD)_B6") (pintype "bidirectional"))
      (node (ref "U2") (pin "P$3") (pinfunction "CMD/DI_P$3") (pintype "bidirectional"))
    )
    (net (code "114") (name "SD_D0") (class "Default")
      (node (ref "R2") (pin "1") (pinfunction "1_1") (pintype "passive"))
      (node (ref "U1") (pin "5") (pinfunction "GPIO4(SDMMC1_D0)_5") (pintype "bidirectional"))
      (node (ref "U1") (pin "B5") (pinfunction "GPIO4(SDMMC1_D0)_B5") (pintype "bidirectional"))
      (node (ref "U2") (pin "P$7") (pinfunction "D0/DO_P$7") (pintype "bidirectional"))
    )
    (net (code "115") (name "SD_D1") (class "Default")
      (node (ref "R16") (pin "1") (pinfunction "1_1") (pintype "passive"))
      (node (ref "U1") (pin "4") (pinfunction "GPIO3(SDMMC1_D1)_4") (pintype "bidirectional"))
      (node (ref "U1") (pin "B4") (pinfunction "GPIO3(SDMMC1_D1)_B4") (pintype "bidirectional"))
      (node (ref "U2") (pin "P$8") (pinfunction "D1/RSV_P$8") (pintype "bidirectional"))
    )
    (net (code "116") (name "SD_D2") (class "Default")
      (node (ref "R3") (pin "1") (pinfunction "1_1") (pintype "passive"))
      (node (ref "U1") (pin "3") (pinfunction "GPIO2(SDMMC1_D2)_3") (pintype "bidirectional"))
      (node (ref "U1") (pin "B3") (pinfunction "GPIO2(SDMMC1_D2)_B3") (pintype "bidirectional"))
      (node (ref "U2") (pin "P$1") (pinfunction "D2/NC_P$1") (pintype "bidirectional"))
    )
    (net (code "117") (name "SD_D3") (class "Default")
      (node (ref "R4") (pin "1") (pinfunction "1_1") (pintype "passive"))
      (node (ref "U1") (pin "2") (pinfunction "GPIO1(SDMMC1_D3)_2") (pintype "bidirectional"))
      (node (ref "U1") (pin "B2") (pinfunction "GPIO1(SDMMC1_D3)_B2") (pintype "bidirectional"))
      (node (ref "U2") (pin "P$2") (pinfunction "D3/CS_P$2") (pintype "bidirectional"))
    )
    (net (code "118") (name "TAC_SWITCH_1") (class "Default")
      (node (ref "SW_5") (pin "2") (pinfunction "P_2") (pintype "passive"))
      (node (ref "U1") (pin "32") (pinfunction "GPIO25(ADC10)_32") (pintype "bidirectional"))
      (node (ref "U1") (pin "B32") (pinfunction "GPIO25(ADC10)_B32") (pintype "bidirectional"))
    )
    (net (code "119") (name "TAC_SWITCH_2") (class "Default")
      (node (ref "SW_6") (pin "2") (pinfunction "P_2") (pintype "passive"))
      (node (ref "U1") (pin "33") (pinfunction "GPIO26(SAI2_SD_A)_33") (pintype "bidirectional"))
      (node (ref "U1") (pin "B33") (pinfunction "GPIO26(SAI2_SD_A)_B33") (pintype "bidirectional"))
    )
    (net (code "120") (name "TAC_SWITCH_3") (class "Default")
      (node (ref "SW_7") (pin "2") (pinfunction "P_2") (pintype "passive"))
      (node (ref "U1") (pin "8") (pinfunction "GPIO7(SPI1_NSS)_8") (pintype "bidirectional"))
      (node (ref "U1") (pin "B8") (pinfunction "GPIO7(SPI1_NSS)_B8") (pintype "bidirectional"))
    )
    (net (code "121") (name "USB_OTG_FS_D+") (class "Default")
      (node (ref "U1") (pin "37") (pinfunction "GPIO30(USB_HS_D+)_37") (pintype "bidirectional"))
      (node (ref "U1") (pin "B37") (pinfunction "GPIO30(USB_HS_D+)_B37") (pintype "bidirectional"))
    )
    (net (code "122") (name "USB_OTG_FS_D-") (class "Default")
      (node (ref "U1") (pin "36") (pinfunction "GPIO29(USB_HS_D_-)_36") (pintype "bidirectional"))
      (node (ref "U1") (pin "B36") (pinfunction "GPIO29(USB_HS_D_-)_B36") (pintype "bidirectional"))
    )
    (net (code "123") (name "USB_OTG_FS_ID") (class "Default")
      (node (ref "U1") (pin "1") (pinfunction "GPIO0(USB_HS_ID)_1") (pintype "bidirectional"))
      (node (ref "U1") (pin "B1") (pinfunction "GPIO0(USB_HS_ID)_B1") (pintype "bidirectional"))
    )
    (net (code "124") (name "V_AUDIOBIAS") (class "Default")
      (node (ref "R36") (pin "2") (pinfunction "2_2") (pintype "passive"))
      (node (ref "R38") (pin "2") (pinfunction "2_2") (pintype "passive"))
      (node (ref "U6") (pin "13") (pinfunction "-IN_13") (pintype "input"))
      (node (ref "U6") (pin "14") (pinfunction "OUT_14") (pintype "output"))
    )
    (net (code "125") (name "unconnected-(J8-RING-Pad3)") (class "Default")
      (node (ref "J8") (pin "3") (pinfunction "RING_3") (pintype "passive"))
    )
    (net (code "126") (name "unconnected-(J8-RING_SW-Pad6)") (class "Default")
      (node (ref "J8") (pin "6") (pinfunction "RING_SW_6") (pintype "passive"))
    )
    (net (code "127") (name "unconnected-(J8-TIP_SW-Pad5)") (class "Default")
      (node (ref "J8") (pin "5") (pinfunction "TIP_SW_5") (pintype "passive"))
    )
    (net (code "128") (name "unconnected-(J9-RING-Pad3)") (class "Default")
      (node (ref "J9") (pin "3") (pinfunction "RING_3") (pintype "passive"))
    )
    (net (code "129") (name "unconnected-(J9-RING_SW-Pad6)") (class "Default")
      (node (ref "J9") (pin "6") (pinfunction "RING_SW_6") (pintype "passive"))
    )
    (net (code "130") (name "unconnected-(J10-RING_SW-Pad6)") (class "Default")
      (node (ref "J10") (pin "6") (pinfunction "RING_SW_6") (pintype "passive"))
    )
    (net (code "131") (name "unconnected-(J10-TIP_SW-Pad5)") (class "Default")
      (node (ref "J10") (pin "5") (pinfunction "TIP_SW_5") (pintype "passive"))
    )
    (net (code "132") (name "unconnected-(J12-RING-Pad3)") (class "Default")
      (node (ref "J12") (pin "3") (pinfunction "RING_3") (pintype "passive"))
    )
    (net (code "133") (name "unconnected-(J12-RING_SW-Pad6)") (class "Default")
      (node (ref "J12") (pin "6") (pinfunction "RING_SW_6") (pintype "passive"))
    )
    (net (code "134") (name "unconnected-(J12-TIP_SW-Pad5)") (class "Default")
      (node (ref "J12") (pin "5") (pinfunction "TIP_SW_5") (pintype "passive"))
    )
    (net (code "135") (name "unconnected-(J13-RING-Pad3)") (class "Default")
      (node (ref "J13") (pin "3") (pinfunction "RING_3") (pintype "passive"))
    )
    (net (code "136") (name "unconnected-(J13-RING_SW-Pad6)") (class "Default")
      (node (ref "J13") (pin "6") (pinfunction "RING_SW_6") (pintype "passive"))
    )
    (net (code "137") (name "unconnected-(J13-TIP_SW-Pad5)") (class "Default")
      (node (ref "J13") (pin "5") (pinfunction "TIP_SW_5") (pintype "passive"))
    )
    (net (code "138") (name "unconnected-(U3-LED12-Pad19)") (class "Default")
      (node (ref "U3") (pin "19") (pinfunction "LED12_19") (pintype "bidirectional"))
    )
    (net (code "139") (name "unconnected-(U3-LED13-Pad20)") (class "Default")
      (node (ref "U3") (pin "20") (pinfunction "LED13_20") (pintype "bidirectional"))
    )
    (net (code "140") (name "unconnected-(U3-LED14-Pad21)") (class "Default")
      (node (ref "U3") (pin "21") (pinfunction "LED14_21") (pintype "bidirectional"))
    )
    (net (code "141") (name "unconnected-(U3-LED15-Pad22)") (class "Default")
      (node (ref "U3") (pin "22") (pinfunction "LED15_22") (pintype "bidirectional"))
    )
  )
)
